# 1_AT32_FOC_CORE_schdoc.net
KiCad netlist of a schematic drawn in Altium Designer
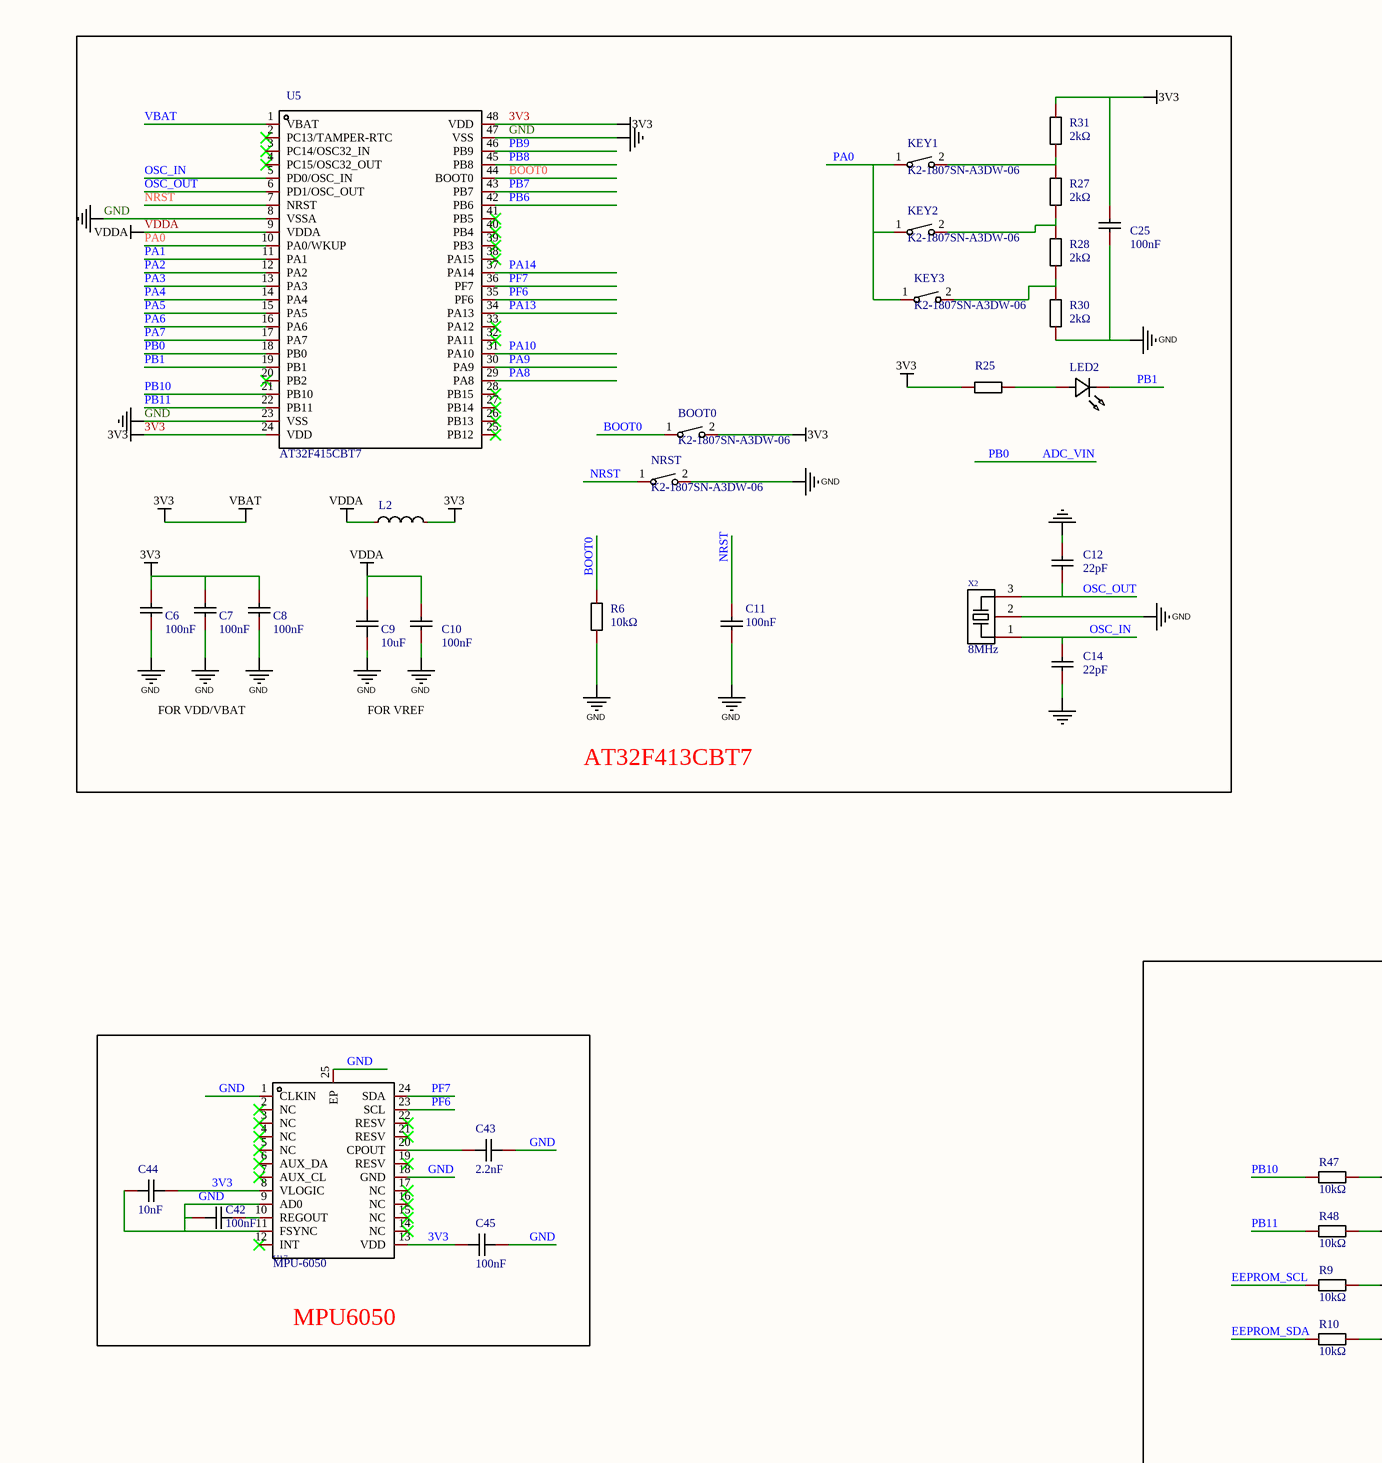
[diagram p0: 1_AT32_FOC_CORE.schdoc.schdoc, top left]
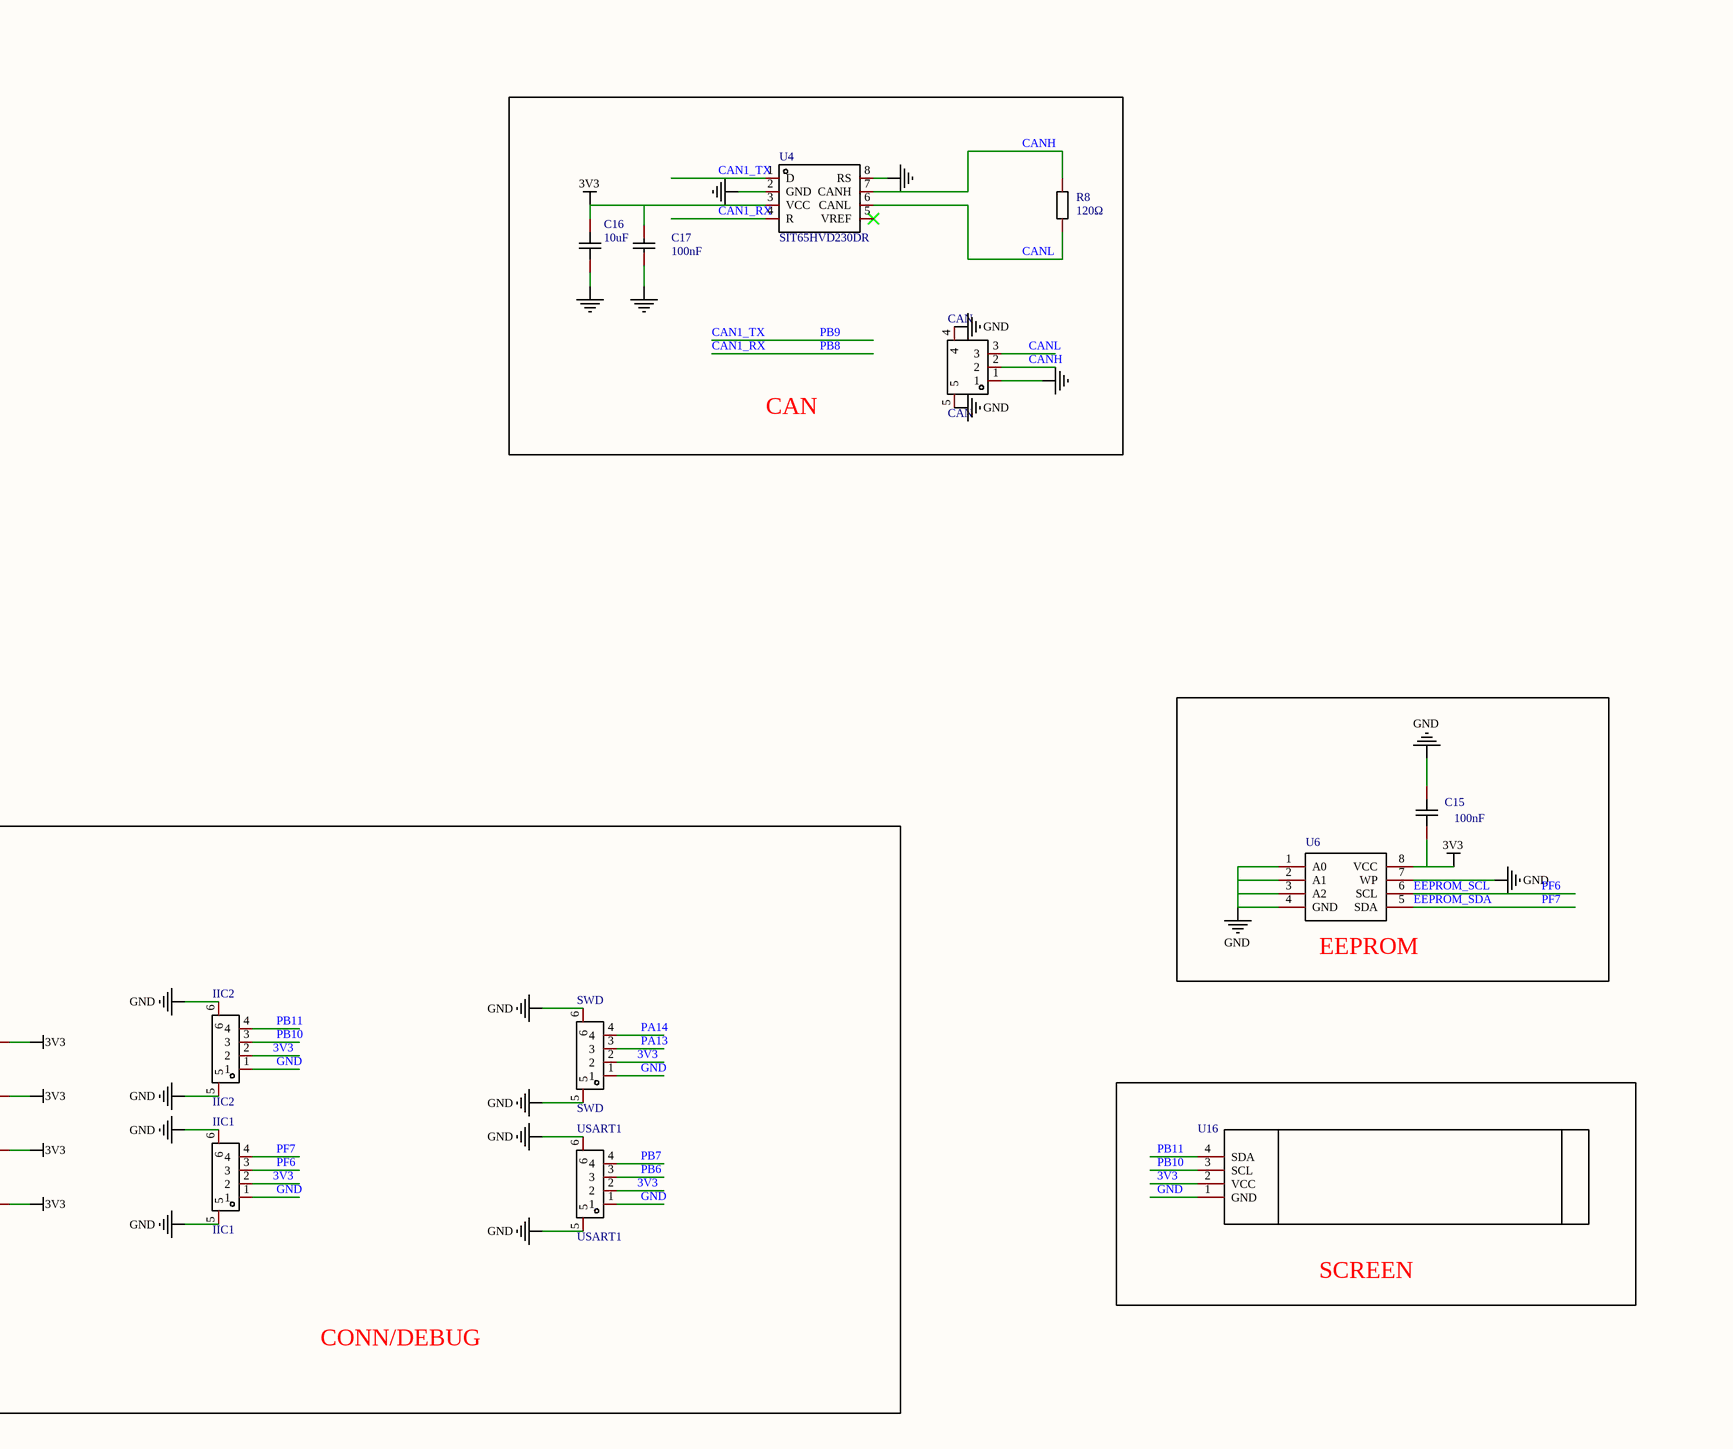
[diagram p1: 1_AT32_FOC_CORE.schdoc.schdoc, top middle]
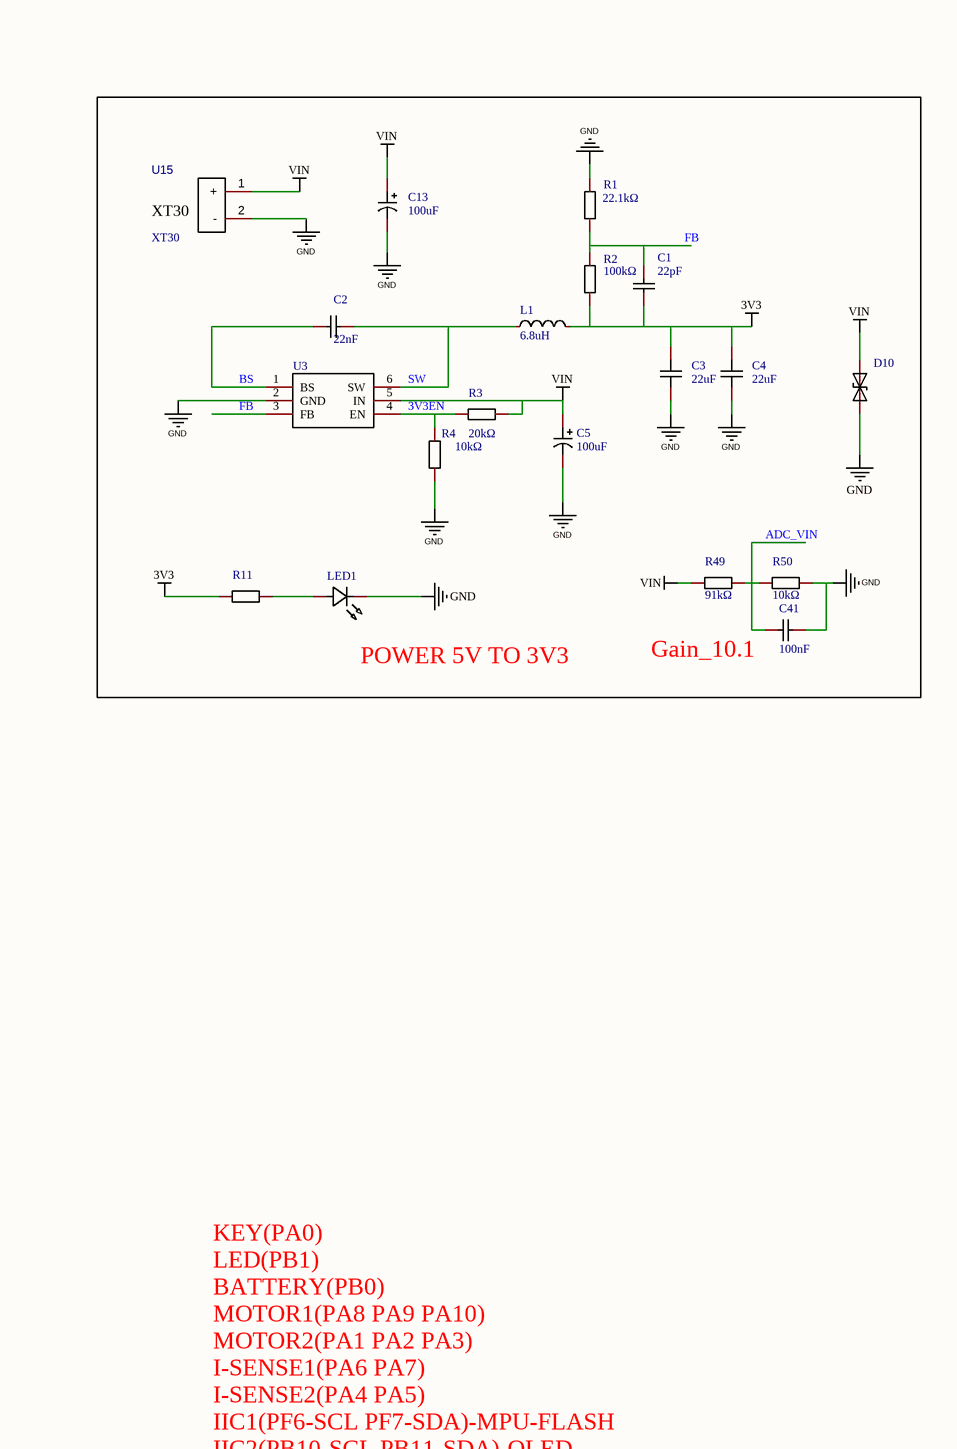
[diagram p2: 1_AT32_FOC_CORE.schdoc.schdoc, top right]
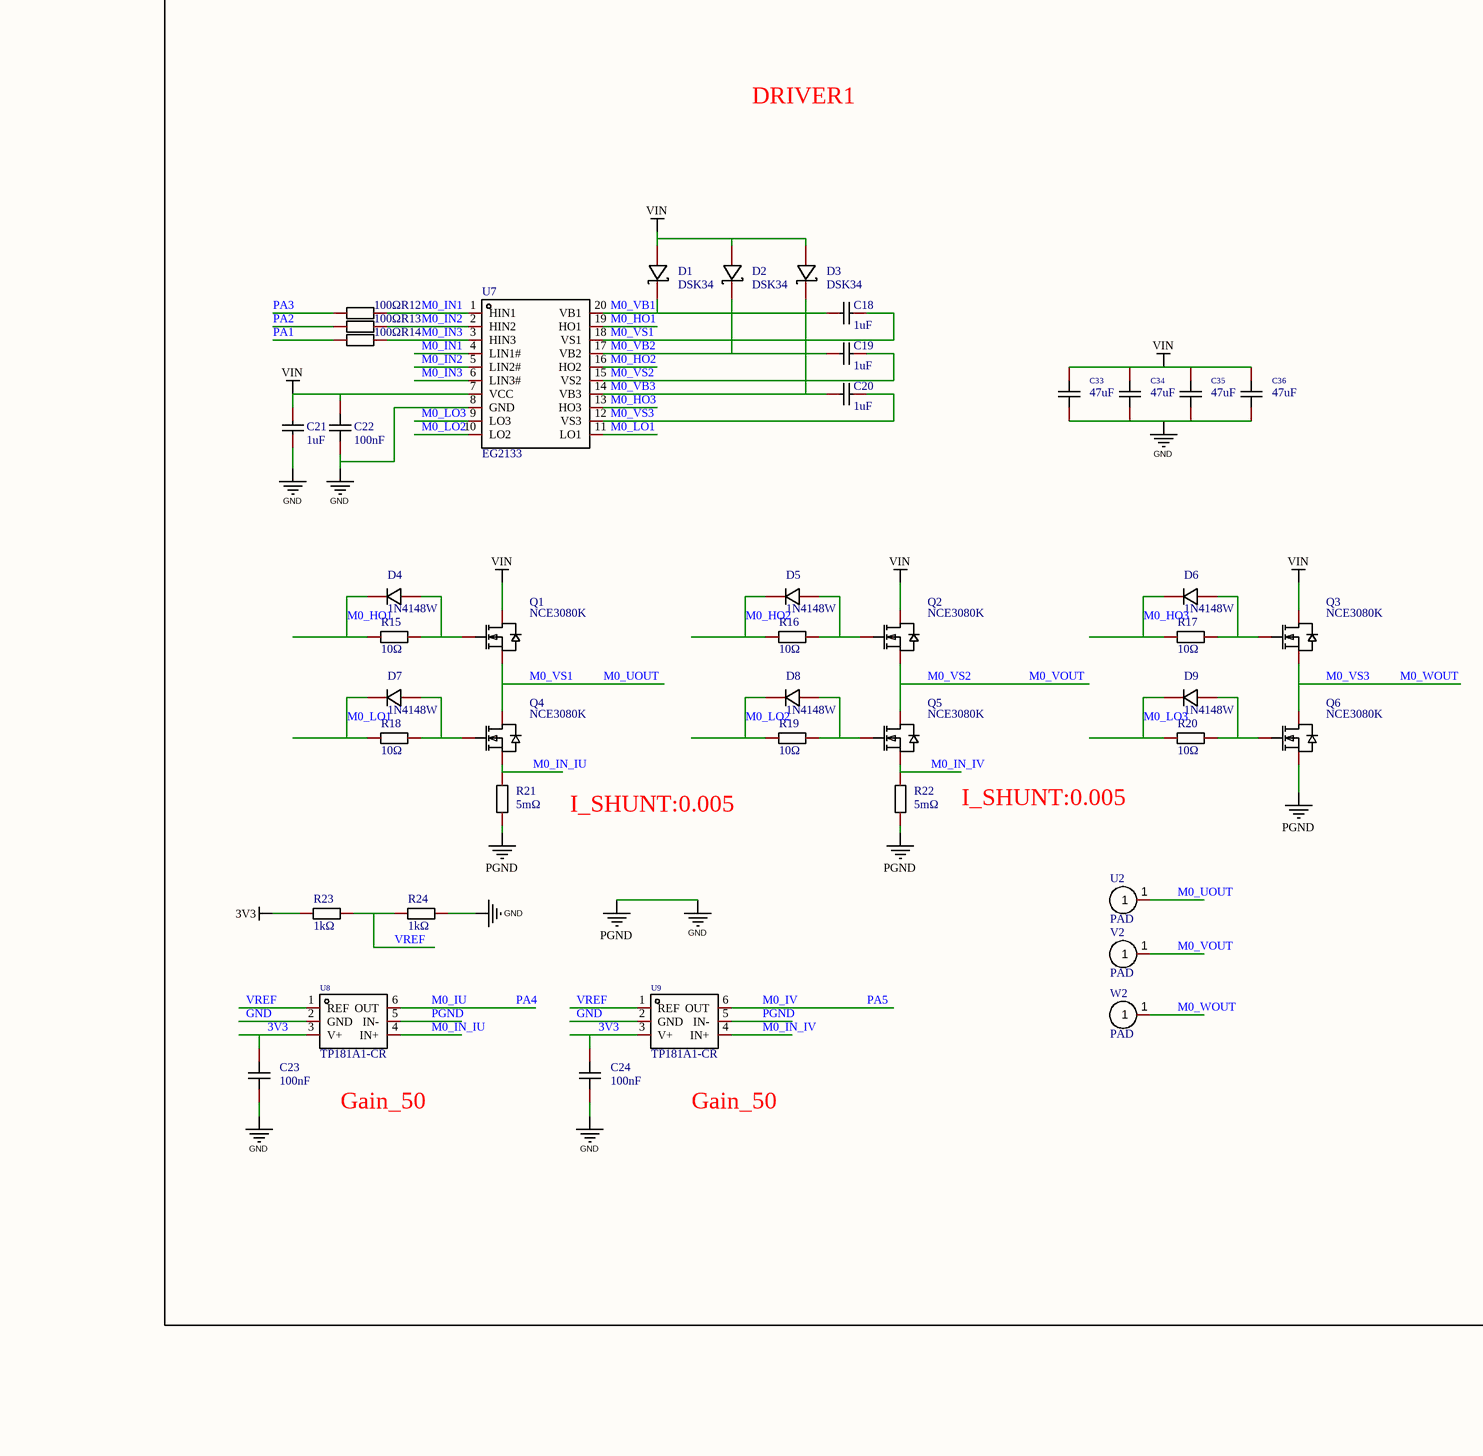
[diagram p3: 1_AT32_FOC_CORE.schdoc.schdoc, bottom left]
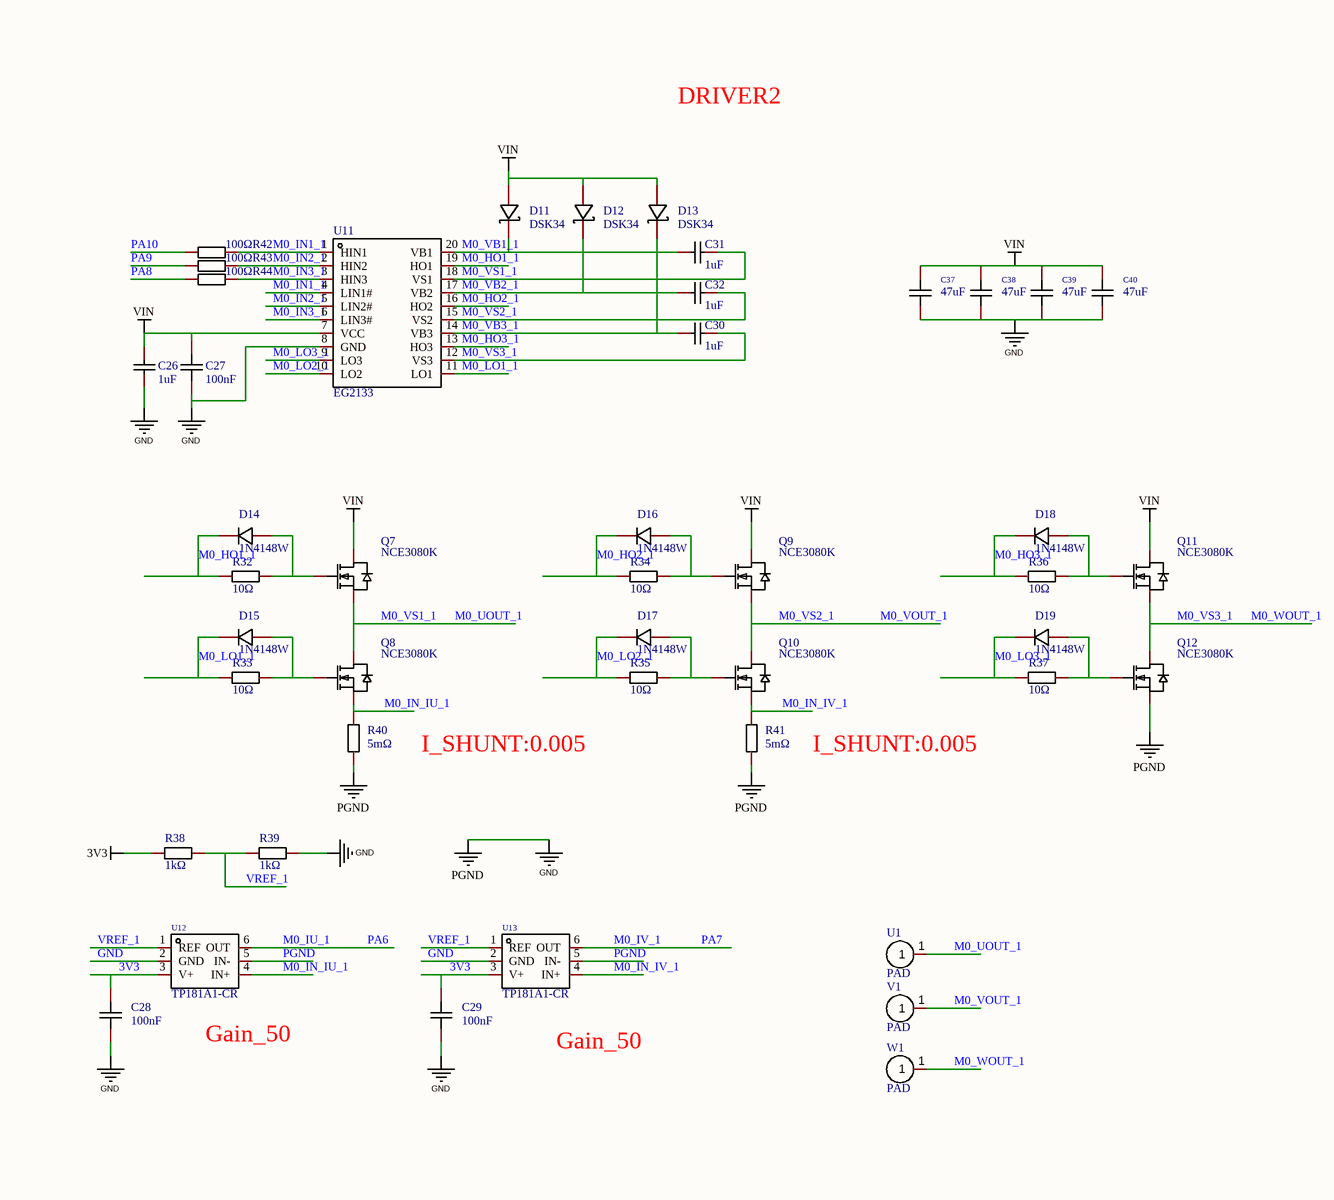
[diagram p4: 1_AT32_FOC_CORE.schdoc.schdoc, bottom middle]

(export (version "E")
  (design (tool "Eeschema 10.0.6"))
  (components
    (comp (ref "BOOT0")
      (value "K2-1807SN-A3DW-06")
      (fields (field (name "NAME") "K2-1807SN-A3DW-06") (field (name "MANUFACTURER") "韩国韩荣"))
      (libsource (lib "altium-import") (part "root_0_K2-1807SN-A3DW-06_"))
    )
    (comp (ref "C1")
      (value "22pF")
      (fields
        (field (name "MANUFACTURER") "SAMSUNG(三星)")
        (field (name "MANUFACTURER PART") "CL10C220JB8NNNC")
        (field (name "TOLERANCE") "±5%")
      )
      (libsource (lib "altium-import") (part "root_1_CL10C220JB8NNNC_"))
    )
    (comp (ref "C2")
      (value "22nF")
      (fields
        (field (name "MANUFACTURER") "SAMSUNG(三星)")
        (field (name "MANUFACTURER PART") "CL10B223KB8NNNC")
        (field (name "TOLERANCE") "±10%")
      )
      (libsource (lib "altium-import") (part "root_0_CL10B223KB8NNNC_"))
    )
    (comp (ref "C3")
      (value "22uF")
      (fields
        (field (name "NAME") "22uF")
        (field (name "MANUFACTURER") "SAMSUNG(三星)")
        (field (name "MANUFACTURER PART") "CL21A226MAQNNNE")
        (field (name "TOLERANCE") "±20%")
      )
      (libsource (lib "altium-import") (part "root_1_CL21A226MAQNNNE_C45783_"))
    )
    (comp (ref "C4")
      (value "22uF")
      (fields
        (field (name "NAME") "22uF")
        (field (name "MANUFACTURER") "SAMSUNG(三星)")
        (field (name "MANUFACTURER PART") "CL21A226MAQNNNE")
        (field (name "TOLERANCE") "±20%")
      )
      (libsource (lib "altium-import") (part "root_1_CL21A226MAQNNNE_C45783_"))
    )
    (comp (ref "C5")
      (value "100uF")
      (fields
        (field (name "NAME") "100uF")
        (field (name "MANUFACTURER") "CapXon(丰宾)")
        (field (name "MANUFACTURER PART") "PM101M025E077PTR")
        (field (name "TOLERANCE") "±20%")
      )
      (libsource (lib "altium-import") (part "root_3_PM101M025E077PTR_"))
    )
    (comp (ref "C6")
      (value "100nF")
      (fields
        (field (name "MANUFACTURER") "FH(风华)")
        (field (name "MANUFACTURER PART") "0603B104K500NT")
        (field (name "TOLERANCE") "±10%")
      )
      (libsource (lib "altium-import") (part "root_1_0603B104K500NT_"))
    )
    (comp (ref "C7")
      (value "100nF")
      (fields
        (field (name "MANUFACTURER") "FH(风华)")
        (field (name "MANUFACTURER PART") "0603B104K500NT")
        (field (name "TOLERANCE") "±10%")
      )
      (libsource (lib "altium-import") (part "root_1_0603B104K500NT_"))
    )
    (comp (ref "C8")
      (value "100nF")
      (fields
        (field (name "MANUFACTURER") "FH(风华)")
        (field (name "MANUFACTURER PART") "0603B104K500NT")
        (field (name "TOLERANCE") "±10%")
      )
      (libsource (lib "altium-import") (part "root_1_0603B104K500NT_"))
    )
    (comp (ref "C9")
      (value "10uF")
      (fields
        (field (name "MANUFACTURER") "SAMSUNG(三星)")
        (field (name "MANUFACTURER PART") "CL10A106KP8NNNC")
        (field (name "TOLERANCE") "±10%")
      )
      (libsource (lib "altium-import") (part "root_1_CL10A106KP8NNNC_"))
    )
    (comp (ref "C10")
      (value "100nF")
      (fields
        (field (name "MANUFACTURER") "FH(风华)")
        (field (name "MANUFACTURER PART") "0603B104K500NT")
        (field (name "TOLERANCE") "±10%")
      )
      (libsource (lib "altium-import") (part "root_1_0603B104K500NT_"))
    )
    (comp (ref "C11")
      (value "100nF")
      (fields
        (field (name "MANUFACTURER") "FH(风华)")
        (field (name "MANUFACTURER PART") "0603B104K500NT")
        (field (name "TOLERANCE") "±10%")
      )
      (libsource (lib "altium-import") (part "root_1_0603B104K500NT_"))
    )
    (comp (ref "C12")
      (value "22pF")
      (fields
        (field (name "MANUFACTURER") "SAMSUNG(三星)")
        (field (name "MANUFACTURER PART") "CL10C220JB8NNNC")
        (field (name "TOLERANCE") "±5%")
      )
      (libsource (lib "altium-import") (part "root_1_CL10C220JB8NNNC_"))
    )
    (comp (ref "C13")
      (value "100uF")
      (fields
        (field (name "NAME") "100uF")
        (field (name "MANUFACTURER") "CapXon(丰宾)")
        (field (name "MANUFACTURER PART") "PM101M025E077PTR")
        (field (name "TOLERANCE") "±20%")
      )
      (libsource (lib "altium-import") (part "root_3_PM101M025E077PTR_"))
    )
    (comp (ref "C14")
      (value "22pF")
      (fields
        (field (name "MANUFACTURER") "SAMSUNG(三星)")
        (field (name "MANUFACTURER PART") "CL10C220JB8NNNC")
        (field (name "TOLERANCE") "±5%")
      )
      (libsource (lib "altium-import") (part "root_1_CL10C220JB8NNNC_"))
    )
    (comp (ref "C15")
      (value "100nF")
      (description "容值:100nF;精度:±10%;额定电压:50V;材质(温度系数):X7R;")
      (fields
        (field (name "MANUFACTURER") "YAGEO(国巨)")
        (field (name "MANUFACTURER PART") "CC0603KRX7R9BB104")
      )
      (libsource (lib "altium-import") (part "root_1_CC0603KRX7R9BB104_"))
    )
    (comp (ref "C16")
      (value "10uF")
      (fields
        (field (name "MANUFACTURER") "SAMSUNG(三星)")
        (field (name "MANUFACTURER PART") "CL10A106KP8NNNC")
        (field (name "TOLERANCE") "±10%")
      )
      (libsource (lib "altium-import") (part "root_1_CL10A106KP8NNNC_"))
    )
    (comp (ref "C17")
      (value "100nF")
      (fields
        (field (name "MANUFACTURER") "FH(风华)")
        (field (name "MANUFACTURER PART") "0603B104K500NT")
        (field (name "TOLERANCE") "±10%")
      )
      (libsource (lib "altium-import") (part "root_1_0603B104K500NT_"))
    )
    (comp (ref "C18")
      (value "1uF")
      (fields
        (field (name "NAME") "1uF")
        (field (name "MANUFACTURER") "SAMSUNG(三星)")
        (field (name "MANUFACTURER PART") "CL10A105KB8NNNC")
        (field (name "TOLERANCE") "±10%")
      )
      (libsource (lib "altium-import") (part "root_2_CL10A105KB8NNNC_"))
    )
    (comp (ref "C19")
      (value "1uF")
      (fields
        (field (name "NAME") "1uF")
        (field (name "MANUFACTURER") "SAMSUNG(三星)")
        (field (name "MANUFACTURER PART") "CL10A105KB8NNNC")
        (field (name "TOLERANCE") "±10%")
      )
      (libsource (lib "altium-import") (part "root_2_CL10A105KB8NNNC_"))
    )
    (comp (ref "C20")
      (value "1uF")
      (fields
        (field (name "NAME") "1uF")
        (field (name "MANUFACTURER") "SAMSUNG(三星)")
        (field (name "MANUFACTURER PART") "CL10A105KB8NNNC")
        (field (name "TOLERANCE") "±10%")
      )
      (libsource (lib "altium-import") (part "root_2_CL10A105KB8NNNC_"))
    )
    (comp (ref "C21")
      (value "1uF")
      (fields
        (field (name "NAME") "1uF")
        (field (name "MANUFACTURER") "SAMSUNG(三星)")
        (field (name "MANUFACTURER PART") "CL10A105KB8NNNC")
        (field (name "TOLERANCE") "±10%")
      )
      (libsource (lib "altium-import") (part "root_1_CL10A105KB8NNNC_"))
    )
    (comp (ref "C22")
      (value "100nF")
      (fields
        (field (name "NAME") "100nF")
        (field (name "MANUFACTURER") "YAGEO(国巨)")
        (field (name "MANUFACTURER PART") "CC0603KRX7R9BB104")
        (field (name "TOLERANCE") "±10%")
      )
      (libsource (lib "altium-import") (part "root_1_CC0603KRX7R9BB104_"))
    )
    (comp (ref "C23")
      (value "100nF")
      (fields
        (field (name "NAME") "100nF")
        (field (name "MANUFACTURER") "YAGEO(国巨)")
        (field (name "MANUFACTURER PART") "CC0603KRX7R9BB104")
        (field (name "TOLERANCE") "±10%")
      )
      (libsource (lib "altium-import") (part "root_3_CC0603KRX7R9BB104_"))
    )
    (comp (ref "C24")
      (value "100nF")
      (fields
        (field (name "NAME") "100nF")
        (field (name "MANUFACTURER") "YAGEO(国巨)")
        (field (name "MANUFACTURER PART") "CC0603KRX7R9BB104")
        (field (name "TOLERANCE") "±10%")
      )
      (libsource (lib "altium-import") (part "root_3_CC0603KRX7R9BB104_"))
    )
    (comp (ref "C25")
      (value "100nF")
      (fields
        (field (name "MANUFACTURER") "FH(风华)")
        (field (name "MANUFACTURER PART") "0603B104K500NT")
        (field (name "TOLERANCE") "±10%")
      )
      (libsource (lib "altium-import") (part "root_1_0603B104K500NT_"))
    )
    (comp (ref "C26")
      (value "1uF")
      (fields
        (field (name "NAME") "1uF")
        (field (name "MANUFACTURER") "SAMSUNG(三星)")
        (field (name "MANUFACTURER PART") "CL10A105KB8NNNC")
        (field (name "TOLERANCE") "±10%")
      )
      (libsource (lib "altium-import") (part "root_1_CL10A105KB8NNNC_"))
    )
    (comp (ref "C27")
      (value "100nF")
      (fields
        (field (name "NAME") "100nF")
        (field (name "MANUFACTURER") "YAGEO(国巨)")
        (field (name "MANUFACTURER PART") "CC0603KRX7R9BB104")
        (field (name "TOLERANCE") "±10%")
      )
      (libsource (lib "altium-import") (part "root_1_CC0603KRX7R9BB104_"))
    )
    (comp (ref "C28")
      (value "100nF")
      (fields
        (field (name "NAME") "100nF")
        (field (name "MANUFACTURER") "YAGEO(国巨)")
        (field (name "MANUFACTURER PART") "CC0603KRX7R9BB104")
        (field (name "TOLERANCE") "±10%")
      )
      (libsource (lib "altium-import") (part "root_3_CC0603KRX7R9BB104_"))
    )
    (comp (ref "C29")
      (value "100nF")
      (fields
        (field (name "NAME") "100nF")
        (field (name "MANUFACTURER") "YAGEO(国巨)")
        (field (name "MANUFACTURER PART") "CC0603KRX7R9BB104")
        (field (name "TOLERANCE") "±10%")
      )
      (libsource (lib "altium-import") (part "root_3_CC0603KRX7R9BB104_"))
    )
    (comp (ref "C30")
      (value "1uF")
      (fields
        (field (name "NAME") "1uF")
        (field (name "MANUFACTURER") "SAMSUNG(三星)")
        (field (name "MANUFACTURER PART") "CL10A105KB8NNNC")
        (field (name "TOLERANCE") "±10%")
      )
      (libsource (lib "altium-import") (part "root_2_CL10A105KB8NNNC_"))
    )
    (comp (ref "C31")
      (value "1uF")
      (fields
        (field (name "NAME") "1uF")
        (field (name "MANUFACTURER") "SAMSUNG(三星)")
        (field (name "MANUFACTURER PART") "CL10A105KB8NNNC")
        (field (name "TOLERANCE") "±10%")
      )
      (libsource (lib "altium-import") (part "root_2_CL10A105KB8NNNC_"))
    )
    (comp (ref "C32")
      (value "1uF")
      (fields
        (field (name "NAME") "1uF")
        (field (name "MANUFACTURER") "SAMSUNG(三星)")
        (field (name "MANUFACTURER PART") "CL10A105KB8NNNC")
        (field (name "TOLERANCE") "±10%")
      )
      (libsource (lib "altium-import") (part "root_2_CL10A105KB8NNNC_"))
    )
    (comp (ref "C33")
      (value "47uF")
      (fields
        (field (name "NAME") "47uF")
        (field (name "MANUFACTURER") "muRata(村田)")
        (field (name "MANUFACTURER PART") "GRM31CR61E476ME44L")
        (field (name "TOLERANCE") "±20%")
      )
      (libsource (lib "altium-import") (part "root_3_GRM31CR61E476ME44L_"))
    )
    (comp (ref "C34")
      (value "47uF")
      (fields
        (field (name "NAME") "47uF")
        (field (name "MANUFACTURER") "muRata(村田)")
        (field (name "MANUFACTURER PART") "GRM31CR61E476ME44L")
        (field (name "TOLERANCE") "±20%")
      )
      (libsource (lib "altium-import") (part "root_3_GRM31CR61E476ME44L_"))
    )
    (comp (ref "C35")
      (value "47uF")
      (fields
        (field (name "NAME") "47uF")
        (field (name "MANUFACTURER") "muRata(村田)")
        (field (name "MANUFACTURER PART") "GRM31CR61E476ME44L")
        (field (name "TOLERANCE") "±20%")
      )
      (libsource (lib "altium-import") (part "root_3_GRM31CR61E476ME44L_"))
    )
    (comp (ref "C36")
      (value "47uF")
      (fields
        (field (name "NAME") "47uF")
        (field (name "MANUFACTURER") "muRata(村田)")
        (field (name "MANUFACTURER PART") "GRM31CR61E476ME44L")
        (field (name "TOLERANCE") "±20%")
      )
      (libsource (lib "altium-import") (part "root_3_GRM31CR61E476ME44L_"))
    )
    (comp (ref "C37")
      (value "47uF")
      (fields
        (field (name "NAME") "47uF")
        (field (name "MANUFACTURER") "muRata(村田)")
        (field (name "MANUFACTURER PART") "GRM31CR61E476ME44L")
        (field (name "TOLERANCE") "±20%")
      )
      (libsource (lib "altium-import") (part "root_3_GRM31CR61E476ME44L_"))
    )
    (comp (ref "C38")
      (value "47uF")
      (fields
        (field (name "NAME") "47uF")
        (field (name "MANUFACTURER") "muRata(村田)")
        (field (name "MANUFACTURER PART") "GRM31CR61E476ME44L")
        (field (name "TOLERANCE") "±20%")
      )
      (libsource (lib "altium-import") (part "root_3_GRM31CR61E476ME44L_"))
    )
    (comp (ref "C39")
      (value "47uF")
      (fields
        (field (name "NAME") "47uF")
        (field (name "MANUFACTURER") "muRata(村田)")
        (field (name "MANUFACTURER PART") "GRM31CR61E476ME44L")
        (field (name "TOLERANCE") "±20%")
      )
      (libsource (lib "altium-import") (part "root_3_GRM31CR61E476ME44L_"))
    )
    (comp (ref "C40")
      (value "47uF")
      (fields
        (field (name "NAME") "47uF")
        (field (name "MANUFACTURER") "muRata(村田)")
        (field (name "MANUFACTURER PART") "GRM31CR61E476ME44L")
        (field (name "TOLERANCE") "±20%")
      )
      (libsource (lib "altium-import") (part "root_3_GRM31CR61E476ME44L_"))
    )
    (comp (ref "C41")
      (value "100nF")
      (fields
        (field (name "MANUFACTURER") "FH(风华)")
        (field (name "MANUFACTURER PART") "0603B104K500NT")
        (field (name "TOLERANCE") "±10%")
      )
      (libsource (lib "altium-import") (part "root_2_0603B104K500NT_"))
    )
    (comp (ref "C42")
      (value "100nF")
      (description "容值:100nF;精度:±10%;额定电压:50V;材质(温度系数):X7R;")
      (fields
        (field (name "MANUFACTURER") "YAGEO(国巨)")
        (field (name "MANUFACTURER PART") "CC0603KRX7R9BB104")
      )
      (libsource (lib "altium-import") (part "root_2_CC0603KRX7R9BB104_"))
    )
    (comp (ref "C43")
      (value "2.2nF")
      (description "容值:100nF;精度:±10%;额定电压:50V;材质(温度系数):X7R;")
      (fields
        (field (name "MANUFACTURER") "YAGEO(国巨)")
        (field (name "MANUFACTURER PART") "CC0603KRX7R9BB104")
      )
      (libsource (lib "altium-import") (part "root_2_CC0603KRX7R9BB104_"))
    )
    (comp (ref "C44")
      (value "10nF")
      (description "容值:100nF;精度:±10%;额定电压:50V;材质(温度系数):X7R;")
      (fields
        (field (name "MANUFACTURER") "YAGEO(国巨)")
        (field (name "MANUFACTURER PART") "CC0603KRX7R9BB104")
      )
      (libsource (lib "altium-import") (part "root_2_CC0603KRX7R9BB104_"))
    )
    (comp (ref "C45")
      (value "100nF")
      (description "容值:100nF;精度:±10%;额定电压:50V;材质(温度系数):X7R;")
      (fields
        (field (name "MANUFACTURER") "YAGEO(国巨)")
        (field (name "MANUFACTURER PART") "CC0603KRX7R9BB104")
      )
      (libsource (lib "altium-import") (part "root_2_CC0603KRX7R9BB104_"))
    )
    (comp (ref "CAN")
      (value "CAN")
      (description "参考系列:SH;间距:1mm;插针结构:1x3P;排数:1;每排PIN数:3;行距:-;公母:公型插针;安装方式:卧贴;额定电流:500mA;工作温度范围:-25℃~+85℃;")
      (fields (field (name "NAME") "CAN") (field (name "MANUFACTURER") "JS(钜硕电子)"))
      (libsource (lib "altium-import") (part "root_2_AFC10-S03QCA-00_"))
    )
    (comp (ref "D1")
      (value "DSK34")
      (description "直流反向耐压(Vr):40V;平均整流电流(Io):3A;正向压降(Vf):550mV@3A;")
      (fields (field (name "NAME") "DSK34") (field (name "MANUFACTURER") "MDD"))
      (libsource (lib "altium-import") (part "root_1_DSK34_C41029_"))
    )
    (comp (ref "D2")
      (value "DSK34")
      (description "直流反向耐压(Vr):40V;平均整流电流(Io):3A;正向压降(Vf):550mV@3A;")
      (fields (field (name "NAME") "DSK34") (field (name "MANUFACTURER") "MDD"))
      (libsource (lib "altium-import") (part "root_1_DSK34_C41029_"))
    )
    (comp (ref "D3")
      (value "DSK34")
      (description "直流反向耐压(Vr):40V;平均整流电流(Io):3A;正向压降(Vf):550mV@3A;")
      (fields (field (name "NAME") "DSK34") (field (name "MANUFACTURER") "MDD"))
      (libsource (lib "altium-import") (part "root_1_DSK34_C41029_"))
    )
    (comp (ref "D4")
      (value "1N4148W")
      (description "二极管配置:独立式;功率:400mW;直流反向耐压(Vr):75V;平均整流电流(Io):150mA;正向压降(Vf):1V@50mA;反向恢复时间(trr):4ns;")
      (fields (field (name "NAME") "1N4148W") (field (name "MANUFACTURER") "ST(先科)"))
      (libsource (lib "altium-import") (part "root_0_1N4148W_C81598_"))
    )
    (comp (ref "D5")
      (value "1N4148W")
      (description "二极管配置:独立式;功率:400mW;直流反向耐压(Vr):75V;平均整流电流(Io):150mA;正向压降(Vf):1V@50mA;反向恢复时间(trr):4ns;")
      (fields (field (name "NAME") "1N4148W") (field (name "MANUFACTURER") "ST(先科)"))
      (libsource (lib "altium-import") (part "root_0_1N4148W_C81598_"))
    )
    (comp (ref "D6")
      (value "1N4148W")
      (description "二极管配置:独立式;功率:400mW;直流反向耐压(Vr):75V;平均整流电流(Io):150mA;正向压降(Vf):1V@50mA;反向恢复时间(trr):4ns;")
      (fields (field (name "NAME") "1N4148W") (field (name "MANUFACTURER") "ST(先科)"))
      (libsource (lib "altium-import") (part "root_0_1N4148W_C81598_"))
    )
    (comp (ref "D7")
      (value "1N4148W")
      (description "二极管配置:独立式;功率:400mW;直流反向耐压(Vr):75V;平均整流电流(Io):150mA;正向压降(Vf):1V@50mA;反向恢复时间(trr):4ns;")
      (fields (field (name "NAME") "1N4148W") (field (name "MANUFACTURER") "ST(先科)"))
      (libsource (lib "altium-import") (part "root_0_1N4148W_C81598_"))
    )
    (comp (ref "D8")
      (value "1N4148W")
      (description "二极管配置:独立式;功率:400mW;直流反向耐压(Vr):75V;平均整流电流(Io):150mA;正向压降(Vf):1V@50mA;反向恢复时间(trr):4ns;")
      (fields (field (name "NAME") "1N4148W") (field (name "MANUFACTURER") "ST(先科)"))
      (libsource (lib "altium-import") (part "root_0_1N4148W_C81598_"))
    )
    (comp (ref "D9")
      (value "1N4148W")
      (description "二极管配置:独立式;功率:400mW;直流反向耐压(Vr):75V;平均整流电流(Io):150mA;正向压降(Vf):1V@50mA;反向恢复时间(trr):4ns;")
      (fields (field (name "NAME") "1N4148W") (field (name "MANUFACTURER") "ST(先科)"))
      (libsource (lib "altium-import") (part "root_0_1N4148W_C81598_"))
    )
    (comp (ref "D10")
      (value "SMAJ12CA/TR13")
      (fields (field (name "MANUFACTURER") "Brightking(君耀电子)"))
      (libsource (lib "altium-import") (part "root_1_SMAJ12CA/TR13_"))
    )
    (comp (ref "D11")
      (value "DSK34")
      (description "直流反向耐压(Vr):40V;平均整流电流(Io):3A;正向压降(Vf):550mV@3A;")
      (fields (field (name "NAME") "DSK34") (field (name "MANUFACTURER") "MDD"))
      (libsource (lib "altium-import") (part "root_1_DSK34_C41029_"))
    )
    (comp (ref "D12")
      (value "DSK34")
      (description "直流反向耐压(Vr):40V;平均整流电流(Io):3A;正向压降(Vf):550mV@3A;")
      (fields (field (name "NAME") "DSK34") (field (name "MANUFACTURER") "MDD"))
      (libsource (lib "altium-import") (part "root_1_DSK34_C41029_"))
    )
    (comp (ref "D13")
      (value "DSK34")
      (description "直流反向耐压(Vr):40V;平均整流电流(Io):3A;正向压降(Vf):550mV@3A;")
      (fields (field (name "NAME") "DSK34") (field (name "MANUFACTURER") "MDD"))
      (libsource (lib "altium-import") (part "root_1_DSK34_C41029_"))
    )
    (comp (ref "D14")
      (value "1N4148W")
      (description "二极管配置:独立式;功率:400mW;直流反向耐压(Vr):75V;平均整流电流(Io):150mA;正向压降(Vf):1V@50mA;反向恢复时间(trr):4ns;")
      (fields (field (name "NAME") "1N4148W") (field (name "MANUFACTURER") "ST(先科)"))
      (libsource (lib "altium-import") (part "root_0_1N4148W_C81598_"))
    )
    (comp (ref "D15")
      (value "1N4148W")
      (description "二极管配置:独立式;功率:400mW;直流反向耐压(Vr):75V;平均整流电流(Io):150mA;正向压降(Vf):1V@50mA;反向恢复时间(trr):4ns;")
      (fields (field (name "NAME") "1N4148W") (field (name "MANUFACTURER") "ST(先科)"))
      (libsource (lib "altium-import") (part "root_0_1N4148W_C81598_"))
    )
    (comp (ref "D16")
      (value "1N4148W")
      (description "二极管配置:独立式;功率:400mW;直流反向耐压(Vr):75V;平均整流电流(Io):150mA;正向压降(Vf):1V@50mA;反向恢复时间(trr):4ns;")
      (fields (field (name "NAME") "1N4148W") (field (name "MANUFACTURER") "ST(先科)"))
      (libsource (lib "altium-import") (part "root_0_1N4148W_C81598_"))
    )
    (comp (ref "D17")
      (value "1N4148W")
      (description "二极管配置:独立式;功率:400mW;直流反向耐压(Vr):75V;平均整流电流(Io):150mA;正向压降(Vf):1V@50mA;反向恢复时间(trr):4ns;")
      (fields (field (name "NAME") "1N4148W") (field (name "MANUFACTURER") "ST(先科)"))
      (libsource (lib "altium-import") (part "root_0_1N4148W_C81598_"))
    )
    (comp (ref "D18")
      (value "1N4148W")
      (description "二极管配置:独立式;功率:400mW;直流反向耐压(Vr):75V;平均整流电流(Io):150mA;正向压降(Vf):1V@50mA;反向恢复时间(trr):4ns;")
      (fields (field (name "NAME") "1N4148W") (field (name "MANUFACTURER") "ST(先科)"))
      (libsource (lib "altium-import") (part "root_0_1N4148W_C81598_"))
    )
    (comp (ref "D19")
      (value "1N4148W")
      (description "二极管配置:独立式;功率:400mW;直流反向耐压(Vr):75V;平均整流电流(Io):150mA;正向压降(Vf):1V@50mA;反向恢复时间(trr):4ns;")
      (fields (field (name "NAME") "1N4148W") (field (name "MANUFACTURER") "ST(先科)"))
      (libsource (lib "altium-import") (part "root_0_1N4148W_C81598_"))
    )
    (comp (ref "IIC1")
      (value "IIC1")
      (description "插针结构:1x4P;间距:1mm;公母:公;安装方式:卧贴;行距:-;排数:1;每排PIN数:4;参考系列:SH;额定电流:500mA;工作温度范围:-25℃~+85℃;")
      (fields (field (name "NAME") "IIC1") (field (name "MANUFACTURER") "JS(钜硕电子)"))
      (libsource (lib "altium-import") (part "root_2_AFC10-S04QCA-00_"))
    )
    (comp (ref "IIC2")
      (value "IIC2")
      (description "插针结构:1x4P;间距:1mm;公母:公;安装方式:卧贴;行距:-;排数:1;每排PIN数:4;参考系列:SH;额定电流:500mA;工作温度范围:-25℃~+85℃;")
      (fields (field (name "NAME") "IIC2") (field (name "MANUFACTURER") "JS(钜硕电子)"))
      (libsource (lib "altium-import") (part "root_2_AFC10-S04QCA-00_"))
    )
    (comp (ref "KEY1")
      (value "K2-1807SN-A3DW-06")
      (fields (field (name "NAME") "K2-1807SN-A3DW-06") (field (name "MANUFACTURER") "韩国韩荣"))
      (libsource (lib "altium-import") (part "root_0_K2-1807SN-A3DW-06_"))
    )
    (comp (ref "KEY2")
      (value "K2-1807SN-A3DW-06")
      (fields (field (name "NAME") "K2-1807SN-A3DW-06") (field (name "MANUFACTURER") "韩国韩荣"))
      (libsource (lib "altium-import") (part "root_0_K2-1807SN-A3DW-06_"))
    )
    (comp (ref "KEY3")
      (value "K2-1807SN-A3DW-06")
      (fields (field (name "NAME") "K2-1807SN-A3DW-06") (field (name "MANUFACTURER") "韩国韩荣"))
      (libsource (lib "altium-import") (part "root_0_K2-1807SN-A3DW-06_"))
    )
    (comp (ref "L1")
      (value "6.8uH")
      (fields (field (name "Comment") "0630 6.8uH"))
      (libsource (lib "altium-import") (part "root_0_0630 6.8uH_"))
    )
    (comp (ref "L2")
      (value "CMH160808B3R3MT")
      (description "电感值:3.3uH;精度:±20%;额定电流:-;直流电阻(DCR):-;")
      (fields (field (name "MANUFACTURER") "FH(风华)") (field (name "TOLERANCE") "±20%"))
      (libsource (lib "altium-import") (part "root_0_CMH160808B3R3MT_"))
    )
    (comp (ref "LED1")
      (value "XL-1608UBC-04")
      (fields (field (name "MANUFACTURER") "XINGLIGHT(成兴光)"))
      (libsource (lib "altium-import") (part "root_2_XL-1608UBC-04_"))
    )
    (comp (ref "LED2")
      (value "XL-1608UBC-04")
      (fields (field (name "MANUFACTURER") "XINGLIGHT(成兴光)"))
      (libsource (lib "altium-import") (part "root_2_XL-1608UBC-04_"))
    )
    (comp (ref "NRST")
      (value "K2-1807SN-A3DW-06")
      (fields (field (name "NAME") "K2-1807SN-A3DW-06") (field (name "MANUFACTURER") "韩国韩荣"))
      (libsource (lib "altium-import") (part "root_0_K2-1807SN-A3DW-06_"))
    )
    (comp (ref "Q1")
      (value "NCE3080K")
      (fields (field (name "NAME") "NCE3080K") (field (name "MANUFACTURER") "NCE(无锡新洁能)"))
      (libsource (lib "altium-import") (part "root_0_NCE3080K_"))
    )
    (comp (ref "Q2")
      (value "NCE3080K")
      (fields (field (name "NAME") "NCE3080K") (field (name "MANUFACTURER") "NCE(无锡新洁能)"))
      (libsource (lib "altium-import") (part "root_0_NCE3080K_"))
    )
    (comp (ref "Q3")
      (value "NCE3080K")
      (fields (field (name "NAME") "NCE3080K") (field (name "MANUFACTURER") "NCE(无锡新洁能)"))
      (libsource (lib "altium-import") (part "root_0_NCE3080K_"))
    )
    (comp (ref "Q4")
      (value "NCE3080K")
      (fields (field (name "NAME") "NCE3080K") (field (name "MANUFACTURER") "NCE(无锡新洁能)"))
      (libsource (lib "altium-import") (part "root_0_NCE3080K_"))
    )
    (comp (ref "Q5")
      (value "NCE3080K")
      (fields (field (name "NAME") "NCE3080K") (field (name "MANUFACTURER") "NCE(无锡新洁能)"))
      (libsource (lib "altium-import") (part "root_0_NCE3080K_"))
    )
    (comp (ref "Q6")
      (value "NCE3080K")
      (fields (field (name "NAME") "NCE3080K") (field (name "MANUFACTURER") "NCE(无锡新洁能)"))
      (libsource (lib "altium-import") (part "root_0_NCE3080K_"))
    )
    (comp (ref "Q7")
      (value "NCE3080K")
      (fields (field (name "NAME") "NCE3080K") (field (name "MANUFACTURER") "NCE(无锡新洁能)"))
      (libsource (lib "altium-import") (part "root_0_NCE3080K_"))
    )
    (comp (ref "Q8")
      (value "NCE3080K")
      (fields (field (name "NAME") "NCE3080K") (field (name "MANUFACTURER") "NCE(无锡新洁能)"))
      (libsource (lib "altium-import") (part "root_0_NCE3080K_"))
    )
    (comp (ref "Q9")
      (value "NCE3080K")
      (fields (field (name "NAME") "NCE3080K") (field (name "MANUFACTURER") "NCE(无锡新洁能)"))
      (libsource (lib "altium-import") (part "root_0_NCE3080K_"))
    )
    (comp (ref "Q10")
      (value "NCE3080K")
      (fields (field (name "NAME") "NCE3080K") (field (name "MANUFACTURER") "NCE(无锡新洁能)"))
      (libsource (lib "altium-import") (part "root_0_NCE3080K_"))
    )
    (comp (ref "Q11")
      (value "NCE3080K")
      (fields (field (name "NAME") "NCE3080K") (field (name "MANUFACTURER") "NCE(无锡新洁能)"))
      (libsource (lib "altium-import") (part "root_0_NCE3080K_"))
    )
    (comp (ref "Q12")
      (value "NCE3080K")
      (fields (field (name "NAME") "NCE3080K") (field (name "MANUFACTURER") "NCE(无锡新洁能)"))
      (libsource (lib "altium-import") (part "root_0_NCE3080K_"))
    )
    (comp (ref "R1")
      (value "22.1kΩ")
      (description "电阻类型:厚膜电阻;阻值:22.1kΩ;精度:±1%;功率:100mW;")
      (fields
        (field (name "MANUFACTURER") "UNI-ROYAL(厚声)")
        (field (name "MANUFACTURER PART") "0603WAF2212T5E")
      )
      (libsource (lib "altium-import") (part "root_1_0603WAF2212T5E_"))
    )
    (comp (ref "R2")
      (value "100kΩ")
      (fields
        (field (name "MANUFACTURER") "UNI-ROYAL(厚声)")
        (field (name "MANUFACTURER PART") "0603WAF1003T5E")
        (field (name "TOLERANCE") "±1%")
      )
      (libsource (lib "altium-import") (part "root_1_0603WAF1003T5E_"))
    )
    (comp (ref "R3")
      (value "20kΩ")
      (fields
        (field (name "MANUFACTURER") "UNI-ROYAL(厚声)")
        (field (name "MANUFACTURER PART") "0603WAF2002T5E")
        (field (name "TOLERANCE") "±1%")
      )
      (libsource (lib "altium-import") (part "root_0_0603WAF2002T5E_"))
    )
    (comp (ref "R4")
      (value "10kΩ")
      (description "电阻类型:厚膜电阻;阻值:10kΩ;精度:±1%;功率:100mW;温度系数:±100ppm/℃;最大工作电压:75V;工作温度范围:-55℃~+155℃;")
      (fields
        (field (name "MANUFACTURER") "UNI-ROYAL(厚声)")
        (field (name "MANUFACTURER PART") "0603WAF1002T5E")
      )
      (libsource (lib "altium-import") (part "root_1_0603WAF1002T5E_"))
    )
    (comp (ref "R6")
      (value "10kΩ")
      (fields
        (field (name "MANUFACTURER") "UNI-ROYAL(厚声)")
        (field (name "MANUFACTURER PART") "0603WAF1002T5E")
        (field (name "TOLERANCE") "±1%")
      )
      (libsource (lib "altium-import") (part "root_1_0603WAF1002T5E_"))
    )
    (comp (ref "R8")
      (value "120Ω")
      (fields
        (field (name "MANUFACTURER") "UNI-ROYAL(厚声)")
        (field (name "MANUFACTURER PART") "0603WAF1200T5E")
        (field (name "TOLERANCE") "±1%")
      )
      (libsource (lib "altium-import") (part "root_3_0603WAF1200T5E_"))
    )
    (comp (ref "R9")
      (value "10kΩ")
      (fields
        (field (name "NAME") "10kΩ")
        (field (name "MANUFACTURER") "UNI-ROYAL(厚声)")
        (field (name "MANUFACTURER PART") "0603WAF1002T5E")
        (field (name "TOLERANCE") "±1%")
      )
      (libsource (lib "altium-import") (part "root_0_0603WAF1002T5E_"))
    )
    (comp (ref "R10")
      (value "10kΩ")
      (fields
        (field (name "NAME") "10kΩ")
        (field (name "MANUFACTURER") "UNI-ROYAL(厚声)")
        (field (name "MANUFACTURER PART") "0603WAF1002T5E")
        (field (name "TOLERANCE") "±1%")
      )
      (libsource (lib "altium-import") (part "root_0_0603WAF1002T5E_"))
    )
    (comp (ref "R11")
      (value "5.1kΩ")
      (description "电阻类型:厚膜电阻;阻值:5.1kΩ;精度:±1%;功率:100mW;温度系数:±100ppm/℃;")
      (fields
        (field (name "MANUFACTURER PART") "0603WAF5101T5E")
        (field (name "MANUFACTURER") "UNI-ROYAL(厚声)")
      )
      (libsource (lib "altium-import") (part "root_0_0603WAF5101T5E_"))
    )
    (comp (ref "R12")
      (value "100Ω")
      (description "电阻类型:厚膜电阻;阻值:100Ω;精度:±1%;功率:100mW;")
      (fields
        (field (name "MANUFACTURER") "UNI-ROYAL(厚声)")
        (field (name "MANUFACTURER PART") "0603WAF1000T5E")
      )
      (libsource (lib "altium-import") (part "root_0_0603WAF1000T5E_"))
    )
    (comp (ref "R13")
      (value "100Ω")
      (description "电阻类型:厚膜电阻;阻值:100Ω;精度:±1%;功率:100mW;")
      (fields
        (field (name "MANUFACTURER") "UNI-ROYAL(厚声)")
        (field (name "MANUFACTURER PART") "0603WAF1000T5E")
      )
      (libsource (lib "altium-import") (part "root_0_0603WAF1000T5E_"))
    )
    (comp (ref "R14")
      (value "100Ω")
      (description "电阻类型:厚膜电阻;阻值:100Ω;精度:±1%;功率:100mW;")
      (fields
        (field (name "MANUFACTURER") "UNI-ROYAL(厚声)")
        (field (name "MANUFACTURER PART") "0603WAF1000T5E")
      )
      (libsource (lib "altium-import") (part "root_0_0603WAF1000T5E_"))
    )
    (comp (ref "R15")
      (value "10Ω")
      (fields
        (field (name "NAME") "10Ω")
        (field (name "MANUFACTURER") "UNI-ROYAL(厚声)")
        (field (name "MANUFACTURER PART") "0805W8F100JT5E")
        (field (name "TOLERANCE") "±1%")
      )
      (libsource (lib "altium-import") (part "root_0_0805W8F100JT5E_"))
    )
    (comp (ref "R16")
      (value "10Ω")
      (fields
        (field (name "NAME") "10Ω")
        (field (name "MANUFACTURER") "UNI-ROYAL(厚声)")
        (field (name "MANUFACTURER PART") "0805W8F100JT5E")
        (field (name "TOLERANCE") "±1%")
      )
      (libsource (lib "altium-import") (part "root_0_0805W8F100JT5E_"))
    )
    (comp (ref "R17")
      (value "10Ω")
      (fields
        (field (name "NAME") "10Ω")
        (field (name "MANUFACTURER") "UNI-ROYAL(厚声)")
        (field (name "MANUFACTURER PART") "0805W8F100JT5E")
        (field (name "TOLERANCE") "±1%")
      )
      (libsource (lib "altium-import") (part "root_0_0805W8F100JT5E_"))
    )
    (comp (ref "R18")
      (value "10Ω")
      (fields
        (field (name "NAME") "10Ω")
        (field (name "MANUFACTURER") "UNI-ROYAL(厚声)")
        (field (name "MANUFACTURER PART") "0805W8F100JT5E")
        (field (name "TOLERANCE") "±1%")
      )
      (libsource (lib "altium-import") (part "root_0_0805W8F100JT5E_"))
    )
    (comp (ref "R19")
      (value "10Ω")
      (fields
        (field (name "NAME") "10Ω")
        (field (name "MANUFACTURER") "UNI-ROYAL(厚声)")
        (field (name "MANUFACTURER PART") "0805W8F100JT5E")
        (field (name "TOLERANCE") "±1%")
      )
      (libsource (lib "altium-import") (part "root_0_0805W8F100JT5E_"))
    )
    (comp (ref "R20")
      (value "10Ω")
      (fields
        (field (name "NAME") "10Ω")
        (field (name "MANUFACTURER") "UNI-ROYAL(厚声)")
        (field (name "MANUFACTURER PART") "0805W8F100JT5E")
        (field (name "TOLERANCE") "±1%")
      )
      (libsource (lib "altium-import") (part "root_0_0805W8F100JT5E_"))
    )
    (comp (ref "R21")
      (value "5mΩ")
      (fields
        (field (name "NAME") "5mΩ")
        (field (name "MANUFACTURER") "大毅科技")
        (field (name "MANUFACTURER PART") "RLP25FEER005")
        (field (name "TOLERANCE") "±1%")
      )
      (libsource (lib "altium-import") (part "root_1_RLP25FEER005_"))
    )
    (comp (ref "R22")
      (value "5mΩ")
      (fields
        (field (name "NAME") "5mΩ")
        (field (name "MANUFACTURER") "大毅科技")
        (field (name "MANUFACTURER PART") "RLP25FEER005")
        (field (name "TOLERANCE") "±1%")
      )
      (libsource (lib "altium-import") (part "root_1_RLP25FEER005_"))
    )
    (comp (ref "R23")
      (value "1kΩ")
      (fields
        (field (name "NAME") "1kΩ")
        (field (name "MANUFACTURER") "UNI-ROYAL(厚声)")
        (field (name "MANUFACTURER PART") "0603WAF1001T5E")
        (field (name "TOLERANCE") "±1%")
      )
      (libsource (lib "altium-import") (part "root_0_0603WAF1001T5E_"))
    )
    (comp (ref "R24")
      (value "1kΩ")
      (fields
        (field (name "NAME") "1kΩ")
        (field (name "MANUFACTURER") "UNI-ROYAL(厚声)")
        (field (name "MANUFACTURER PART") "0603WAF1001T5E")
        (field (name "TOLERANCE") "±1%")
      )
      (libsource (lib "altium-import") (part "root_0_0603WAF1001T5E_"))
    )
    (comp (ref "R25")
      (value "5.1kΩ")
      (description "电阻类型:厚膜电阻;阻值:5.1kΩ;精度:±1%;功率:100mW;温度系数:±100ppm/℃;")
      (fields
        (field (name "MANUFACTURER PART") "0603WAF5101T5E")
        (field (name "MANUFACTURER") "UNI-ROYAL(厚声)")
      )
      (libsource (lib "altium-import") (part "root_0_0603WAF5101T5E_"))
    )
    (comp (ref "R27")
      (value "2kΩ")
      (fields
        (field (name "MANUFACTURER") "UNI-ROYAL(厚声)")
        (field (name "MANUFACTURER PART") "0603WAF1002T5E")
        (field (name "TOLERANCE") "±1%")
      )
      (libsource (lib "altium-import") (part "root_1_0603WAF1002T5E_"))
    )
    (comp (ref "R28")
      (value "2kΩ")
      (fields
        (field (name "MANUFACTURER") "UNI-ROYAL(厚声)")
        (field (name "MANUFACTURER PART") "0603WAF1002T5E")
        (field (name "TOLERANCE") "±1%")
      )
      (libsource (lib "altium-import") (part "root_1_0603WAF1002T5E_"))
    )
    (comp (ref "R30")
      (value "2kΩ")
      (fields
        (field (name "MANUFACTURER") "UNI-ROYAL(厚声)")
        (field (name "MANUFACTURER PART") "0603WAF1002T5E")
        (field (name "TOLERANCE") "±1%")
      )
      (libsource (lib "altium-import") (part "root_1_0603WAF1002T5E_"))
    )
    (comp (ref "R31")
      (value "2kΩ")
      (fields
        (field (name "MANUFACTURER") "UNI-ROYAL(厚声)")
        (field (name "MANUFACTURER PART") "0603WAF1002T5E")
        (field (name "TOLERANCE") "±1%")
      )
      (libsource (lib "altium-import") (part "root_1_0603WAF1002T5E_"))
    )
    (comp (ref "R32")
      (value "10Ω")
      (fields
        (field (name "NAME") "10Ω")
        (field (name "MANUFACTURER") "UNI-ROYAL(厚声)")
        (field (name "MANUFACTURER PART") "0805W8F100JT5E")
        (field (name "TOLERANCE") "±1%")
      )
      (libsource (lib "altium-import") (part "root_0_0805W8F100JT5E_"))
    )
    (comp (ref "R33")
      (value "10Ω")
      (fields
        (field (name "NAME") "10Ω")
        (field (name "MANUFACTURER") "UNI-ROYAL(厚声)")
        (field (name "MANUFACTURER PART") "0805W8F100JT5E")
        (field (name "TOLERANCE") "±1%")
      )
      (libsource (lib "altium-import") (part "root_0_0805W8F100JT5E_"))
    )
    (comp (ref "R34")
      (value "10Ω")
      (fields
        (field (name "NAME") "10Ω")
        (field (name "MANUFACTURER") "UNI-ROYAL(厚声)")
        (field (name "MANUFACTURER PART") "0805W8F100JT5E")
        (field (name "TOLERANCE") "±1%")
      )
      (libsource (lib "altium-import") (part "root_0_0805W8F100JT5E_"))
    )
    (comp (ref "R35")
      (value "10Ω")
      (fields
        (field (name "NAME") "10Ω")
        (field (name "MANUFACTURER") "UNI-ROYAL(厚声)")
        (field (name "MANUFACTURER PART") "0805W8F100JT5E")
        (field (name "TOLERANCE") "±1%")
      )
      (libsource (lib "altium-import") (part "root_0_0805W8F100JT5E_"))
    )
    (comp (ref "R36")
      (value "10Ω")
      (fields
        (field (name "NAME") "10Ω")
        (field (name "MANUFACTURER") "UNI-ROYAL(厚声)")
        (field (name "MANUFACTURER PART") "0805W8F100JT5E")
        (field (name "TOLERANCE") "±1%")
      )
      (libsource (lib "altium-import") (part "root_0_0805W8F100JT5E_"))
    )
    (comp (ref "R37")
      (value "10Ω")
      (fields
        (field (name "NAME") "10Ω")
        (field (name "MANUFACTURER") "UNI-ROYAL(厚声)")
        (field (name "MANUFACTURER PART") "0805W8F100JT5E")
        (field (name "TOLERANCE") "±1%")
      )
      (libsource (lib "altium-import") (part "root_0_0805W8F100JT5E_"))
    )
    (comp (ref "R38")
      (value "1kΩ")
      (fields
        (field (name "NAME") "1kΩ")
        (field (name "MANUFACTURER") "UNI-ROYAL(厚声)")
        (field (name "MANUFACTURER PART") "0603WAF1001T5E")
        (field (name "TOLERANCE") "±1%")
      )
      (libsource (lib "altium-import") (part "root_0_0603WAF1001T5E_"))
    )
    (comp (ref "R39")
      (value "1kΩ")
      (fields
        (field (name "NAME") "1kΩ")
        (field (name "MANUFACTURER") "UNI-ROYAL(厚声)")
        (field (name "MANUFACTURER PART") "0603WAF1001T5E")
        (field (name "TOLERANCE") "±1%")
      )
      (libsource (lib "altium-import") (part "root_0_0603WAF1001T5E_"))
    )
    (comp (ref "R40")
      (value "5mΩ")
      (fields
        (field (name "NAME") "5mΩ")
        (field (name "MANUFACTURER") "大毅科技")
        (field (name "MANUFACTURER PART") "RLP25FEER005")
        (field (name "TOLERANCE") "±1%")
      )
      (libsource (lib "altium-import") (part "root_1_RLP25FEER005_"))
    )
    (comp (ref "R41")
      (value "5mΩ")
      (fields
        (field (name "NAME") "5mΩ")
        (field (name "MANUFACTURER") "大毅科技")
        (field (name "MANUFACTURER PART") "RLP25FEER005")
        (field (name "TOLERANCE") "±1%")
      )
      (libsource (lib "altium-import") (part "root_1_RLP25FEER005_"))
    )
    (comp (ref "R42")
      (value "100Ω")
      (description "电阻类型:厚膜电阻;阻值:100Ω;精度:±1%;功率:100mW;")
      (fields
        (field (name "MANUFACTURER") "UNI-ROYAL(厚声)")
        (field (name "MANUFACTURER PART") "0603WAF1000T5E")
      )
      (libsource (lib "altium-import") (part "root_0_0603WAF1000T5E_"))
    )
    (comp (ref "R43")
      (value "100Ω")
      (description "电阻类型:厚膜电阻;阻值:100Ω;精度:±1%;功率:100mW;")
      (fields
        (field (name "MANUFACTURER") "UNI-ROYAL(厚声)")
        (field (name "MANUFACTURER PART") "0603WAF1000T5E")
      )
      (libsource (lib "altium-import") (part "root_0_0603WAF1000T5E_"))
    )
    (comp (ref "R44")
      (value "100Ω")
      (description "电阻类型:厚膜电阻;阻值:100Ω;精度:±1%;功率:100mW;")
      (fields
        (field (name "MANUFACTURER") "UNI-ROYAL(厚声)")
        (field (name "MANUFACTURER PART") "0603WAF1000T5E")
      )
      (libsource (lib "altium-import") (part "root_0_0603WAF1000T5E_"))
    )
    (comp (ref "R47")
      (value "10kΩ")
      (fields
        (field (name "NAME") "10kΩ")
        (field (name "MANUFACTURER") "UNI-ROYAL(厚声)")
        (field (name "MANUFACTURER PART") "0603WAF1002T5E")
        (field (name "TOLERANCE") "±1%")
      )
      (libsource (lib "altium-import") (part "root_0_0603WAF1002T5E_"))
    )
    (comp (ref "R48")
      (value "10kΩ")
      (fields
        (field (name "NAME") "10kΩ")
        (field (name "MANUFACTURER") "UNI-ROYAL(厚声)")
        (field (name "MANUFACTURER PART") "0603WAF1002T5E")
        (field (name "TOLERANCE") "±1%")
      )
      (libsource (lib "altium-import") (part "root_0_0603WAF1002T5E_"))
    )
    (comp (ref "R49")
      (value "91kΩ")
      (description "电阻类型:厚膜电阻;阻值:5.1kΩ;精度:±1%;功率:100mW;温度系数:±100ppm/℃;")
      (fields
        (field (name "MANUFACTURER PART") "0603WAF5101T5E")
        (field (name "MANUFACTURER") "UNI-ROYAL(厚声)")
      )
      (libsource (lib "altium-import") (part "root_0_0603WAF5101T5E_"))
    )
    (comp (ref "R50")
      (value "10kΩ")
      (description "电阻类型:厚膜电阻;阻值:5.1kΩ;精度:±1%;功率:100mW;温度系数:±100ppm/℃;")
      (fields
        (field (name "MANUFACTURER PART") "0603WAF5101T5E")
        (field (name "MANUFACTURER") "UNI-ROYAL(厚声)")
      )
      (libsource (lib "altium-import") (part "root_0_0603WAF5101T5E_"))
    )
    (comp (ref "SWD")
      (value "SWD")
      (description "插针结构:1x4P;间距:1mm;公母:公;安装方式:卧贴;行距:-;排数:1;每排PIN数:4;参考系列:SH;额定电流:500mA;工作温度范围:-25℃~+85℃;")
      (fields (field (name "NAME") "SWD") (field (name "MANUFACTURER") "JS(钜硕电子)"))
      (libsource (lib "altium-import") (part "root_2_AFC10-S04QCA-00_"))
    )
    (comp (ref "U1")
      (value "PAD")
      (fields (field (name "NAME") "PAD"))
      (libsource (lib "altium-import") (part "root_1_PAD_"))
    )
    (comp (ref "U2")
      (value "PAD")
      (fields (field (name "NAME") "PAD"))
      (libsource (lib "altium-import") (part "root_1_PAD_"))
    )
    (comp (ref "U3")
      (value "MT2492")
      (description "功能类型:降压型;同步整流:-;输出通道数:-;拓扑结构:-;输入电压:-;输出电流(最大值):-;开关频率:-;")
      (fields (field (name "MANUFACTURER") "西安航天民芯"))
      (libsource (lib "altium-import") (part "root_0_MT2492_"))
    )
    (comp (ref "U4")
      (value "SIT65HVD230DR")
      (description "类型:-;")
      (fields (field (name "NAME") "SIT65HVD230DR") (field (name "MANUFACTURER") "SIT(芯力特)"))
      (libsource (lib "altium-import") (part "root_0_SIT65HVD230DR_"))
    )
    (comp (ref "U5")
      (value "AT32F415CBT7")
      (description "CPU内核:ARM Cortex-M4;CPU最大主频:-;程序存储容量:128KB;程序存储器类型:FLASH;RAM总容量:32KB;GPIO端口数量:-;")
      (fields (field (name "MANUFACTURER") "ARTERY(雅特力)") (field (name "MANUFACTURER PART") "AT32F415CBT7"))
      (libsource (lib "altium-import") (part "root_0_AT32F415CBT7_C528427_"))
    )
    (comp (ref "U6")
      (value "AT24C02C-SSHM-T")
      (description "存储器容量:2Kb (256 x 8);存储器接口类型:I2C;工作电压:1.7V ~ 5.5V;")
      (fields (field (name "MANUFACTURER") "MICROCHIP(美国微芯)"))
      (libsource (lib "altium-import") (part "root_0_AT24C02C-SSHM-T_"))
    )
    (comp (ref "U7")
      (value "EG2133")
      (description "EG2133是一款高性价比的三相半桥驱动芯片，配合六颗Nmos可以组成三相直流无刷电机驱动器。")
      (fields (field (name "NAME") "EG2133") (field (name "MANUFACTURER") "EG(屹晶微)"))
      (libsource (lib "altium-import") (part "root_0_EG2133_C190343_"))
    )
    (comp (ref "U8")
      (value "TP181A1-CR")
      (fields (field (name "NAME") "TP181A1-CR") (field (name "MANUFACTURER") "3PEAK"))
      (libsource (lib "altium-import") (part "root_0_TP181A1-CR_"))
    )
    (comp (ref "U9")
      (value "TP181A1-CR")
      (fields (field (name "NAME") "TP181A1-CR") (field (name "MANUFACTURER") "3PEAK"))
      (libsource (lib "altium-import") (part "root_0_TP181A1-CR_"))
    )
    (comp (ref "U11")
      (value "EG2133")
      (description "EG2133是一款高性价比的三相半桥驱动芯片，配合六颗Nmos可以组成三相直流无刷电机驱动器。")
      (fields (field (name "NAME") "EG2133") (field (name "MANUFACTURER") "EG(屹晶微)"))
      (libsource (lib "altium-import") (part "root_0_EG2133_C190343_"))
    )
    (comp (ref "U12")
      (value "TP181A1-CR")
      (fields (field (name "NAME") "TP181A1-CR") (field (name "MANUFACTURER") "3PEAK"))
      (libsource (lib "altium-import") (part "root_0_TP181A1-CR_"))
    )
    (comp (ref "U13")
      (value "TP181A1-CR")
      (fields (field (name "NAME") "TP181A1-CR") (field (name "MANUFACTURER") "3PEAK"))
      (libsource (lib "altium-import") (part "root_0_TP181A1-CR_"))
    )
    (comp (ref "U15")
      (value "XT30")
      (fields (field (name "NAME") "XT30"))
      (libsource (lib "altium-import") (part "root_0_XT30_"))
    )
    (comp (ref "U16")
      (value "0.91OLED-4P-IIC模块")
      (libsource (lib "altium-import") (part "root_0_0.91OLED-4P-IIC模块_"))
    )
    (comp (ref "U17")
      (value "MPU-6050")
      (description "三轴加速度计和三轴陀螺仪，工作电压：2.375V~3.46V")
      (fields (field (name "NAME") "MPU-6050") (field (name "MANUFACTURER") "TDK InvenSense(应美盛)"))
      (libsource (lib "altium-import") (part "root_0_MPU-6050_"))
    )
    (comp (ref "USART1")
      (value "USART1")
      (description "插针结构:1x4P;间距:1mm;公母:公;安装方式:卧贴;行距:-;排数:1;每排PIN数:4;参考系列:SH;额定电流:500mA;工作温度范围:-25℃~+85℃;")
      (fields (field (name "NAME") "USART1") (field (name "MANUFACTURER") "JS(钜硕电子)"))
      (libsource (lib "altium-import") (part "root_2_AFC10-S04QCA-00_"))
    )
    (comp (ref "V1")
      (value "PAD")
      (fields (field (name "NAME") "PAD"))
      (libsource (lib "altium-import") (part "root_1_PAD_"))
    )
    (comp (ref "V2")
      (value "PAD")
      (fields (field (name "NAME") "PAD"))
      (libsource (lib "altium-import") (part "root_1_PAD_"))
    )
    (comp (ref "W1")
      (value "PAD")
      (fields (field (name "NAME") "PAD"))
      (libsource (lib "altium-import") (part "root_1_PAD_"))
    )
    (comp (ref "W2")
      (value "PAD")
      (fields (field (name "NAME") "PAD"))
      (libsource (lib "altium-import") (part "root_1_PAD_"))
    )
    (comp (ref "X2")
      (value "8MHz")
      (description "频率:8MHz;频率容差:±0.5%;内置负载电容:10pF;谐振阻抗:40Ω;")
      (fields
        (field (name "NAME") "8MHz")
        (field (name "MANUFACTURER PART") "CSTCE8M00G52-R0")
        (field (name "MANUFACTURER") "muRata(村田)")
      )
      (libsource (lib "altium-import") (part "root_1_CSTCE8M00G52-R0_"))
    )
  )
  (nets
    (net (code "1") (name "/3V3EN") (class "Default")
      (node (ref "R3") (pin "1") (pinfunction "1_1") (pintype "passive"))
      (node (ref "R4") (pin "2") (pinfunction "2_2") (pintype "passive"))
      (node (ref "U3") (pin "4") (pinfunction "EN_4") (pintype "passive"))
    )
    (net (code "2") (name "/ADC_VIN") (class "Default")
      (node (ref "C41") (pin "2") (pinfunction "2_2") (pintype "passive"))
      (node (ref "R49") (pin "2") (pinfunction "2_2") (pintype "passive"))
      (node (ref "R50") (pin "1") (pinfunction "1_1") (pintype "passive"))
      (node (ref "U5") (pin "18") (pinfunction "PB0_18") (pintype "passive"))
    )
    (net (code "3") (name "/BOOT0") (class "Default")
      (node (ref "BOOT0") (pin "1") (pinfunction "1_1") (pintype "passive"))
      (node (ref "R6") (pin "2") (pinfunction "2_2") (pintype "passive"))
      (node (ref "U5") (pin "44") (pinfunction "BOOT0_44") (pintype "passive"))
    )
    (net (code "4") (name "/BS") (class "Default")
      (node (ref "C2") (pin "1") (pinfunction "1_1") (pintype "passive"))
      (node (ref "U3") (pin "1") (pinfunction "BS_1") (pintype "passive"))
    )
    (net (code "5") (name "/CAN1_RX") (class "Default")
      (node (ref "U4") (pin "4") (pinfunction "R_4") (pintype "passive"))
      (node (ref "U5") (pin "45") (pinfunction "PB8_45") (pintype "passive"))
    )
    (net (code "6") (name "/CAN1_TX") (class "Default")
      (node (ref "U4") (pin "1") (pinfunction "D_1") (pintype "passive"))
      (node (ref "U5") (pin "46") (pinfunction "PB9_46") (pintype "passive"))
    )
    (net (code "7") (name "/CANH") (class "Default")
      (node (ref "CAN") (pin "2") (pinfunction "2_2") (pintype "passive"))
      (node (ref "R8") (pin "1") (pinfunction "1_1") (pintype "passive"))
      (node (ref "U4") (pin "7") (pinfunction "CANH_7") (pintype "passive"))
    )
    (net (code "8") (name "/CANL") (class "Default")
      (node (ref "CAN") (pin "3") (pinfunction "3_3") (pintype "passive"))
      (node (ref "R8") (pin "2") (pinfunction "2_2") (pintype "passive"))
      (node (ref "U4") (pin "6") (pinfunction "CANL_6") (pintype "passive"))
    )
    (net (code "9") (name "/EEPROM_SCL") (class "Default")
      (node (ref "IIC1") (pin "3") (pinfunction "3_3") (pintype "passive"))
      (node (ref "R9") (pin "1") (pinfunction "1_1") (pintype "passive"))
      (node (ref "U17") (pin "23") (pinfunction "SCL_23") (pintype "passive"))
      (node (ref "U5") (pin "35") (pinfunction "PF6_35") (pintype "passive"))
      (node (ref "U6") (pin "6") (pinfunction "SCL_6") (pintype "passive"))
    )
    (net (code "10") (name "/EEPROM_SDA") (class "Default")
      (node (ref "IIC1") (pin "4") (pinfunction "4_4") (pintype "passive"))
      (node (ref "R10") (pin "1") (pinfunction "1_1") (pintype "passive"))
      (node (ref "U17") (pin "24") (pinfunction "SDA_24") (pintype "passive"))
      (node (ref "U5") (pin "36") (pinfunction "PF7_36") (pintype "passive"))
      (node (ref "U6") (pin "5") (pinfunction "SDA_5") (pintype "passive"))
    )
    (net (code "11") (name "/FB") (class "Default")
      (node (ref "C1") (pin "2") (pinfunction "2_2") (pintype "passive"))
      (node (ref "R1") (pin "1") (pinfunction "1_1") (pintype "passive"))
      (node (ref "R2") (pin "2") (pinfunction "2_2") (pintype "passive"))
      (node (ref "U3") (pin "3") (pinfunction "FB_3") (pintype "passive"))
    )
    (net (code "12") (name "/M0_HO1") (class "Default")
      (node (ref "D4") (pin "1") (pinfunction "K_1") (pintype "passive"))
      (node (ref "R15") (pin "1") (pinfunction "1_1") (pintype "passive"))
      (node (ref "U7") (pin "19") (pinfunction "HO1_19") (pintype "passive"))
    )
    (net (code "13") (name "/M0_HO1_1") (class "Default")
      (node (ref "D14") (pin "1") (pinfunction "K_1") (pintype "passive"))
      (node (ref "R32") (pin "1") (pinfunction "1_1") (pintype "passive"))
      (node (ref "U11") (pin "19") (pinfunction "HO1_19") (pintype "passive"))
    )
    (net (code "14") (name "/M0_HO2") (class "Default")
      (node (ref "D5") (pin "1") (pinfunction "K_1") (pintype "passive"))
      (node (ref "R16") (pin "1") (pinfunction "1_1") (pintype "passive"))
      (node (ref "U7") (pin "16") (pinfunction "HO2_16") (pintype "passive"))
    )
    (net (code "15") (name "/M0_HO2_1") (class "Default")
      (node (ref "D16") (pin "1") (pinfunction "K_1") (pintype "passive"))
      (node (ref "R34") (pin "1") (pinfunction "1_1") (pintype "passive"))
      (node (ref "U11") (pin "16") (pinfunction "HO2_16") (pintype "passive"))
    )
    (net (code "16") (name "/M0_HO3") (class "Default")
      (node (ref "D6") (pin "1") (pinfunction "K_1") (pintype "passive"))
      (node (ref "R17") (pin "1") (pinfunction "1_1") (pintype "passive"))
      (node (ref "U7") (pin "13") (pinfunction "HO3_13") (pintype "passive"))
    )
    (net (code "17") (name "/M0_HO3_1") (class "Default")
      (node (ref "D18") (pin "1") (pinfunction "K_1") (pintype "passive"))
      (node (ref "R36") (pin "1") (pinfunction "1_1") (pintype "passive"))
      (node (ref "U11") (pin "13") (pinfunction "HO3_13") (pintype "passive"))
    )
    (net (code "18") (name "/M0_IN1") (class "Default")
      (node (ref "R12") (pin "2") (pinfunction "2_2") (pintype "passive"))
      (node (ref "U7") (pin "1") (pinfunction "HIN1_1") (pintype "passive"))
      (node (ref "U7") (pin "4") (pinfunction "LIN1#_4") (pintype "passive"))
    )
    (net (code "19") (name "/M0_IN1_1") (class "Default")
      (node (ref "R42") (pin "2") (pinfunction "2_2") (pintype "passive"))
      (node (ref "U11") (pin "1") (pinfunction "HIN1_1") (pintype "passive"))
      (node (ref "U11") (pin "4") (pinfunction "LIN1#_4") (pintype "passive"))
    )
    (net (code "20") (name "/M0_IN2") (class "Default")
      (node (ref "R13") (pin "2") (pinfunction "2_2") (pintype "passive"))
      (node (ref "U7") (pin "2") (pinfunction "HIN2_2") (pintype "passive"))
      (node (ref "U7") (pin "5") (pinfunction "LIN2#_5") (pintype "passive"))
    )
    (net (code "21") (name "/M0_IN2_1") (class "Default")
      (node (ref "R43") (pin "2") (pinfunction "2_2") (pintype "passive"))
      (node (ref "U11") (pin "2") (pinfunction "HIN2_2") (pintype "passive"))
      (node (ref "U11") (pin "5") (pinfunction "LIN2#_5") (pintype "passive"))
    )
    (net (code "22") (name "/M0_IN3") (class "Default")
      (node (ref "R14") (pin "2") (pinfunction "2_2") (pintype "passive"))
      (node (ref "U7") (pin "3") (pinfunction "HIN3_3") (pintype "passive"))
      (node (ref "U7") (pin "6") (pinfunction "LIN3#_6") (pintype "passive"))
    )
    (net (code "23") (name "/M0_IN3_1") (class "Default")
      (node (ref "R44") (pin "2") (pinfunction "2_2") (pintype "passive"))
      (node (ref "U11") (pin "3") (pinfunction "HIN3_3") (pintype "passive"))
      (node (ref "U11") (pin "6") (pinfunction "LIN3#_6") (pintype "passive"))
    )
    (net (code "24") (name "/M0_IN_IU") (class "Default")
      (node (ref "Q4") (pin "3") (pinfunction "S_3") (pintype "passive"))
      (node (ref "R21") (pin "2") (pinfunction "2_2") (pintype "passive"))
      (node (ref "U8") (pin "4") (pinfunction "IN+_4") (pintype "passive"))
    )
    (net (code "25") (name "/M0_IN_IU_1") (class "Default")
      (node (ref "Q8") (pin "3") (pinfunction "S_3") (pintype "passive"))
      (node (ref "R40") (pin "2") (pinfunction "2_2") (pintype "passive"))
      (node (ref "U12") (pin "4") (pinfunction "IN+_4") (pintype "passive"))
    )
    (net (code "26") (name "/M0_IN_IV") (class "Default")
      (node (ref "Q5") (pin "3") (pinfunction "S_3") (pintype "passive"))
      (node (ref "R22") (pin "2") (pinfunction "2_2") (pintype "passive"))
      (node (ref "U9") (pin "4") (pinfunction "IN+_4") (pintype "passive"))
    )
    (net (code "27") (name "/M0_IN_IV_1") (class "Default")
      (node (ref "Q10") (pin "3") (pinfunction "S_3") (pintype "passive"))
      (node (ref "R41") (pin "2") (pinfunction "2_2") (pintype "passive"))
      (node (ref "U13") (pin "4") (pinfunction "IN+_4") (pintype "passive"))
    )
    (net (code "28") (name "/M0_IU") (class "Default")
      (node (ref "U5") (pin "14") (pinfunction "PA4_14") (pintype "passive"))
      (node (ref "U8") (pin "6") (pinfunction "OUT_6") (pintype "passive"))
    )
    (net (code "29") (name "/M0_IU_1") (class "Default")
      (node (ref "U12") (pin "6") (pinfunction "OUT_6") (pintype "passive"))
      (node (ref "U5") (pin "16") (pinfunction "PA6_16") (pintype "passive"))
    )
    (net (code "30") (name "/M0_IV") (class "Default")
      (node (ref "U5") (pin "15") (pinfunction "PA5_15") (pintype "passive"))
      (node (ref "U9") (pin "6") (pinfunction "OUT_6") (pintype "passive"))
    )
    (net (code "31") (name "/M0_IV_1") (class "Default")
      (node (ref "U13") (pin "6") (pinfunction "OUT_6") (pintype "passive"))
      (node (ref "U5") (pin "17") (pinfunction "PA7_17") (pintype "passive"))
    )
    (net (code "32") (name "/M0_LO1") (class "Default")
      (node (ref "D7") (pin "1") (pinfunction "K_1") (pintype "passive"))
      (node (ref "R18") (pin "1") (pinfunction "1_1") (pintype "passive"))
      (node (ref "U7") (pin "11") (pinfunction "LO1_11") (pintype "passive"))
    )
    (net (code "33") (name "/M0_LO1_1") (class "Default")
      (node (ref "D15") (pin "1") (pinfunction "K_1") (pintype "passive"))
      (node (ref "R33") (pin "1") (pinfunction "1_1") (pintype "passive"))
      (node (ref "U11") (pin "11") (pinfunction "LO1_11") (pintype "passive"))
    )
    (net (code "34") (name "/M0_LO2") (class "Default")
      (node (ref "D8") (pin "1") (pinfunction "K_1") (pintype "passive"))
      (node (ref "R19") (pin "1") (pinfunction "1_1") (pintype "passive"))
      (node (ref "U7") (pin "10") (pinfunction "LO2_10") (pintype "passive"))
    )
    (net (code "35") (name "/M0_LO2_1") (class "Default")
      (node (ref "D17") (pin "1") (pinfunction "K_1") (pintype "passive"))
      (node (ref "R35") (pin "1") (pinfunction "1_1") (pintype "passive"))
      (node (ref "U11") (pin "10") (pinfunction "LO2_10") (pintype "passive"))
    )
    (net (code "36") (name "/M0_LO3") (class "Default")
      (node (ref "D9") (pin "1") (pinfunction "K_1") (pintype "passive"))
      (node (ref "R20") (pin "1") (pinfunction "1_1") (pintype "passive"))
      (node (ref "U7") (pin "9") (pinfunction "LO3_9") (pintype "passive"))
    )
    (net (code "37") (name "/M0_LO3_1") (class "Default")
      (node (ref "D19") (pin "1") (pinfunction "K_1") (pintype "passive"))
      (node (ref "R37") (pin "1") (pinfunction "1_1") (pintype "passive"))
      (node (ref "U11") (pin "9") (pinfunction "LO3_9") (pintype "passive"))
    )
    (net (code "38") (name "/M0_UOUT") (class "Default")
      (node (ref "C18") (pin "1") (pinfunction "1_1") (pintype "passive"))
      (node (ref "Q1") (pin "3") (pinfunction "S_3") (pintype "passive"))
      (node (ref "Q4") (pin "2") (pinfunction "D_2") (pintype "passive"))
      (node (ref "U2") (pin "1") (pinfunction "1_1") (pintype "passive"))
      (node (ref "U7") (pin "18") (pinfunction "VS1_18") (pintype "passive"))
    )
    (net (code "39") (name "/M0_UOUT_1") (class "Default")
      (node (ref "C31") (pin "1") (pinfunction "1_1") (pintype "passive"))
      (node (ref "Q7") (pin "3") (pinfunction "S_3") (pintype "passive"))
      (node (ref "Q8") (pin "2") (pinfunction "D_2") (pintype "passive"))
      (node (ref "U1") (pin "1") (pinfunction "1_1") (pintype "passive"))
      (node (ref "U11") (pin "18") (pinfunction "VS1_18") (pintype "passive"))
    )
    (net (code "40") (name "/M0_VB1") (class "Default")
      (node (ref "C18") (pin "2") (pinfunction "2_2") (pintype "passive"))
      (node (ref "D1") (pin "1") (pinfunction "K_1") (pintype "passive"))
      (node (ref "U7") (pin "20") (pinfunction "VB1_20") (pintype "passive"))
    )
    (net (code "41") (name "/M0_VB1_1") (class "Default")
      (node (ref "C31") (pin "2") (pinfunction "2_2") (pintype "passive"))
      (node (ref "D11") (pin "1") (pinfunction "K_1") (pintype "passive"))
      (node (ref "U11") (pin "20") (pinfunction "VB1_20") (pintype "passive"))
    )
    (net (code "42") (name "/M0_VB2") (class "Default")
      (node (ref "C19") (pin "2") (pinfunction "2_2") (pintype "passive"))
      (node (ref "D2") (pin "1") (pinfunction "K_1") (pintype "passive"))
      (node (ref "U7") (pin "17") (pinfunction "VB2_17") (pintype "passive"))
    )
    (net (code "43") (name "/M0_VB2_1") (class "Default")
      (node (ref "C32") (pin "2") (pinfunction "2_2") (pintype "passive"))
      (node (ref "D12") (pin "1") (pinfunction "K_1") (pintype "passive"))
      (node (ref "U11") (pin "17") (pinfunction "VB2_17") (pintype "passive"))
    )
    (net (code "44") (name "/M0_VB3") (class "Default")
      (node (ref "C20") (pin "2") (pinfunction "2_2") (pintype "passive"))
      (node (ref "D3") (pin "1") (pinfunction "K_1") (pintype "passive"))
      (node (ref "U7") (pin "14") (pinfunction "VB3_14") (pintype "passive"))
    )
    (net (code "45") (name "/M0_VB3_1") (class "Default")
      (node (ref "C30") (pin "2") (pinfunction "2_2") (pintype "passive"))
      (node (ref "D13") (pin "1") (pinfunction "K_1") (pintype "passive"))
      (node (ref "U11") (pin "14") (pinfunction "VB3_14") (pintype "passive"))
    )
    (net (code "46") (name "/M0_VOUT") (class "Default")
      (node (ref "C19") (pin "1") (pinfunction "1_1") (pintype "passive"))
      (node (ref "Q2") (pin "3") (pinfunction "S_3") (pintype "passive"))
      (node (ref "Q5") (pin "2") (pinfunction "D_2") (pintype "passive"))
      (node (ref "U7") (pin "15") (pinfunction "VS2_15") (pintype "passive"))
      (node (ref "V2") (pin "1") (pinfunction "1_1") (pintype "passive"))
    )
    (net (code "47") (name "/M0_VOUT_1") (class "Default")
      (node (ref "C32") (pin "1") (pinfunction "1_1") (pintype "passive"))
      (node (ref "Q10") (pin "2") (pinfunction "D_2") (pintype "passive"))
      (node (ref "Q9") (pin "3") (pinfunction "S_3") (pintype "passive"))
      (node (ref "U11") (pin "15") (pinfunction "VS2_15") (pintype "passive"))
      (node (ref "V1") (pin "1") (pinfunction "1_1") (pintype "passive"))
    )
    (net (code "48") (name "/M0_VS3") (class "Default")
      (node (ref "C20") (pin "1") (pinfunction "1_1") (pintype "passive"))
      (node (ref "Q3") (pin "3") (pinfunction "S_3") (pintype "passive"))
      (node (ref "Q6") (pin "2") (pinfunction "D_2") (pintype "passive"))
      (node (ref "U7") (pin "12") (pinfunction "VS3_12") (pintype "passive"))
      (node (ref "W2") (pin "1") (pinfunction "1_1") (pintype "passive"))
    )
    (net (code "49") (name "/M0_VS3_1") (class "Default")
      (node (ref "C30") (pin "1") (pinfunction "1_1") (pintype "passive"))
      (node (ref "Q11") (pin "3") (pinfunction "S_3") (pintype "passive"))
      (node (ref "Q12") (pin "2") (pinfunction "D_2") (pintype "passive"))
      (node (ref "U11") (pin "12") (pinfunction "VS3_12") (pintype "passive"))
      (node (ref "W1") (pin "1") (pinfunction "1_1") (pintype "passive"))
    )
    (net (code "50") (name "/NRST") (class "Default")
      (node (ref "C11") (pin "2") (pinfunction "2_2") (pintype "passive"))
      (node (ref "NRST") (pin "1") (pinfunction "1_1") (pintype "passive"))
      (node (ref "U5") (pin "7") (pinfunction "NRST_7") (pintype "passive"))
    )
    (net (code "51") (name "/OSC_IN") (class "Default")
      (node (ref "C14") (pin "2") (pinfunction "2_2") (pintype "passive"))
      (node (ref "U5") (pin "5") (pinfunction "PD0/OSC_IN_5") (pintype "passive"))
      (node (ref "X2") (pin "1") (pinfunction "1_1") (pintype "passive"))
    )
    (net (code "52") (name "/OSC_OUT") (class "Default")
      (node (ref "C12") (pin "1") (pinfunction "1_1") (pintype "passive"))
      (node (ref "U5") (pin "6") (pinfunction "PD1/OSC_OUT_6") (pintype "passive"))
      (node (ref "X2") (pin "3") (pinfunction "3_3") (pintype "passive"))
    )
    (net (code "53") (name "/PA0") (class "Default")
      (node (ref "KEY1") (pin "1") (pinfunction "1_1") (pintype "passive"))
      (node (ref "KEY2") (pin "1") (pinfunction "1_1") (pintype "passive"))
      (node (ref "KEY3") (pin "1") (pinfunction "1_1") (pintype "passive"))
      (node (ref "U5") (pin "10") (pinfunction "PA0/WKUP_10") (pintype "passive"))
    )
    (net (code "54") (name "/PA1") (class "Default")
      (node (ref "R14") (pin "1") (pinfunction "1_1") (pintype "passive"))
      (node (ref "U5") (pin "11") (pinfunction "PA1_11") (pintype "passive"))
    )
    (net (code "55") (name "/PA2") (class "Default")
      (node (ref "R13") (pin "1") (pinfunction "1_1") (pintype "passive"))
      (node (ref "U5") (pin "12") (pinfunction "PA2_12") (pintype "passive"))
    )
    (net (code "56") (name "/PA3") (class "Default")
      (node (ref "R12") (pin "1") (pinfunction "1_1") (pintype "passive"))
      (node (ref "U5") (pin "13") (pinfunction "PA3_13") (pintype "passive"))
    )
    (net (code "57") (name "/PA8") (class "Default")
      (node (ref "R44") (pin "1") (pinfunction "1_1") (pintype "passive"))
      (node (ref "U5") (pin "29") (pinfunction "PA8_29") (pintype "passive"))
    )
    (net (code "58") (name "/PA9") (class "Default")
      (node (ref "R43") (pin "1") (pinfunction "1_1") (pintype "passive"))
      (node (ref "U5") (pin "30") (pinfunction "PA9_30") (pintype "passive"))
    )
    (net (code "59") (name "/PA10") (class "Default")
      (node (ref "R42") (pin "1") (pinfunction "1_1") (pintype "passive"))
      (node (ref "U5") (pin "31") (pinfunction "PA10_31") (pintype "passive"))
    )
    (net (code "60") (name "/PA13") (class "Default")
      (node (ref "SWD") (pin "3") (pinfunction "3_3") (pintype "passive"))
      (node (ref "U5") (pin "34") (pinfunction "PA13_34") (pintype "passive"))
    )
    (net (code "61") (name "/PA14") (class "Default")
      (node (ref "SWD") (pin "4") (pinfunction "4_4") (pintype "passive"))
      (node (ref "U5") (pin "37") (pinfunction "PA14_37") (pintype "passive"))
    )
    (net (code "62") (name "/PB1") (class "Default")
      (node (ref "LED2") (pin "1") (pinfunction "K_1") (pintype "passive"))
      (node (ref "U5") (pin "19") (pinfunction "PB1_19") (pintype "passive"))
    )
    (net (code "63") (name "/PB6") (class "Default")
      (node (ref "U5") (pin "42") (pinfunction "PB6_42") (pintype "passive"))
      (node (ref "USART1") (pin "3") (pinfunction "3_3") (pintype "passive"))
    )
    (net (code "64") (name "/PB7") (class "Default")
      (node (ref "U5") (pin "43") (pinfunction "PB7_43") (pintype "passive"))
      (node (ref "USART1") (pin "4") (pinfunction "4_4") (pintype "passive"))
    )
    (net (code "65") (name "/PB10") (class "Default")
      (node (ref "IIC2") (pin "3") (pinfunction "3_3") (pintype "passive"))
      (node (ref "R47") (pin "1") (pinfunction "1_1") (pintype "passive"))
      (node (ref "U16") (pin "3") (pinfunction "SCL_3") (pintype "passive"))
      (node (ref "U5") (pin "21") (pinfunction "PB10_21") (pintype "passive"))
    )
    (net (code "66") (name "/PB11") (class "Default")
      (node (ref "IIC2") (pin "4") (pinfunction "4_4") (pintype "passive"))
      (node (ref "R48") (pin "1") (pinfunction "1_1") (pintype "passive"))
      (node (ref "U16") (pin "4") (pinfunction "SDA_4") (pintype "passive"))
      (node (ref "U5") (pin "22") (pinfunction "PB11_22") (pintype "passive"))
    )
    (net (code "67") (name "/SW") (class "Default")
      (node (ref "C2") (pin "2") (pinfunction "2_2") (pintype "passive"))
      (node (ref "L1") (pin "1") (pinfunction "1_1") (pintype "passive"))
      (node (ref "U3") (pin "6") (pinfunction "SW_6") (pintype "passive"))
    )
    (net (code "68") (name "/VREF") (class "Default")
      (node (ref "R23") (pin "2") (pinfunction "2_2") (pintype "passive"))
      (node (ref "R24") (pin "1") (pinfunction "1_1") (pintype "passive"))
      (node (ref "U8") (pin "1") (pinfunction "REF_1") (pintype "passive"))
      (node (ref "U9") (pin "1") (pinfunction "REF_1") (pintype "passive"))
    )
    (net (code "69") (name "/VREF_1") (class "Default")
      (node (ref "R38") (pin "2") (pinfunction "2_2") (pintype "passive"))
      (node (ref "R39") (pin "1") (pinfunction "1_1") (pintype "passive"))
      (node (ref "U12") (pin "1") (pinfunction "REF_1") (pintype "passive"))
      (node (ref "U13") (pin "1") (pinfunction "REF_1") (pintype "passive"))
    )
    (net (code "70") (name "3V3") (class "Default")
      (node (ref "BOOT0") (pin "2") (pinfunction "2_2") (pintype "passive"))
      (node (ref "C1") (pin "1") (pinfunction "1_1") (pintype "passive"))
      (node (ref "C15") (pin "1") (pinfunction "1_1") (pintype "passive"))
      (node (ref "C16") (pin "2") (pinfunction "2_2") (pintype "passive"))
      (node (ref "C17") (pin "2") (pinfunction "2_2") (pintype "passive"))
      (node (ref "C23") (pin "1") (pinfunction "1_1") (pintype "passive"))
      (node (ref "C24") (pin "1") (pinfunction "1_1") (pintype "passive"))
      (node (ref "C25") (pin "2") (pinfunction "2_2") (pintype "passive"))
      (node (ref "C28") (pin "1") (pinfunction "1_1") (pintype "passive"))
      (node (ref "C29") (pin "1") (pinfunction "1_1") (pintype "passive"))
      (node (ref "C3") (pin "2") (pinfunction "2_2") (pintype "passive"))
      (node (ref "C4") (pin "2") (pinfunction "2_2") (pintype "passive"))
      (node (ref "C44") (pin "1") (pinfunction "1_1") (pintype "passive"))
      (node (ref "C45") (pin "2") (pinfunction "2_2") (pintype "passive"))
      (node (ref "C6") (pin "2") (pinfunction "2_2") (pintype "passive"))
      (node (ref "C7") (pin "2") (pinfunction "2_2") (pintype "passive"))
      (node (ref "C8") (pin "2") (pinfunction "2_2") (pintype "passive"))
      (node (ref "IIC1") (pin "2") (pinfunction "2_2") (pintype "passive"))
      (node (ref "IIC2") (pin "2") (pinfunction "2_2") (pintype "passive"))
      (node (ref "L1") (pin "2") (pinfunction "2_2") (pintype "passive"))
      (node (ref "L2") (pin "2") (pinfunction "2_2") (pintype "passive"))
      (node (ref "R10") (pin "2") (pinfunction "2_2") (pintype "passive"))
      (node (ref "R11") (pin "1") (pinfunction "1_1") (pintype "passive"))
      (node (ref "R2") (pin "1") (pinfunction "1_1") (pintype "passive"))
      (node (ref "R23") (pin "1") (pinfunction "1_1") (pintype "passive"))
      (node (ref "R25") (pin "1") (pinfunction "1_1") (pintype "passive"))
      (node (ref "R31") (pin "2") (pinfunction "2_2") (pintype "passive"))
      (node (ref "R38") (pin "1") (pinfunction "1_1") (pintype "passive"))
      (node (ref "R47") (pin "2") (pinfunction "2_2") (pintype "passive"))
      (node (ref "R48") (pin "2") (pinfunction "2_2") (pintype "passive"))
      (node (ref "R9") (pin "2") (pinfunction "2_2") (pintype "passive"))
      (node (ref "SWD") (pin "2") (pinfunction "2_2") (pintype "passive"))
      (node (ref "U12") (pin "3") (pinfunction "V+_3") (pintype "passive"))
      (node (ref "U13") (pin "3") (pinfunction "V+_3") (pintype "passive"))
      (node (ref "U16") (pin "2") (pinfunction "VCC_2") (pintype "passive"))
      (node (ref "U17") (pin "13") (pinfunction "VDD_13") (pintype "passive"))
      (node (ref "U17") (pin "8") (pinfunction "VLOGIC_8") (pintype "passive"))
      (node (ref "U4") (pin "3") (pinfunction "VCC_3") (pintype "passive"))
      (node (ref "U5") (pin "1") (pinfunction "VBAT_1") (pintype "passive"))
      (node (ref "U5") (pin "24") (pinfunction "VDD_24") (pintype "passive"))
      (node (ref "U5") (pin "48") (pinfunction "VDD_48") (pintype "passive"))
      (node (ref "U6") (pin "8") (pinfunction "VCC_8") (pintype "passive"))
      (node (ref "U8") (pin "3") (pinfunction "V+_3") (pintype "passive"))
      (node (ref "U9") (pin "3") (pinfunction "V+_3") (pintype "passive"))
      (node (ref "USART1") (pin "2") (pinfunction "2_2") (pintype "passive"))
    )
    (net (code "71") (name "GND") (class "Default")
      (node (ref "C10") (pin "1") (pinfunction "1_1") (pintype "passive"))
      (node (ref "C11") (pin "1") (pinfunction "1_1") (pintype "passive"))
      (node (ref "C12") (pin "2") (pinfunction "2_2") (pintype "passive"))
      (node (ref "C13") (pin "2") (pinfunction "2_2") (pintype "passive"))
      (node (ref "C14") (pin "1") (pinfunction "1_1") (pintype "passive"))
      (node (ref "C15") (pin "2") (pinfunction "2_2") (pintype "passive"))
      (node (ref "C16") (pin "1") (pinfunction "1_1") (pintype "passive"))
      (node (ref "C17") (pin "1") (pinfunction "1_1") (pintype "passive"))
      (node (ref "C21") (pin "1") (pinfunction "1_1") (pintype "passive"))
      (node (ref "C22") (pin "1") (pinfunction "1_1") (pintype "passive"))
      (node (ref "C23") (pin "2") (pinfunction "2_2") (pintype "passive"))
      (node (ref "C24") (pin "2") (pinfunction "2_2") (pintype "passive"))
      (node (ref "C25") (pin "1") (pinfunction "1_1") (pintype "passive"))
      (node (ref "C26") (pin "1") (pinfunction "1_1") (pintype "passive"))
      (node (ref "C27") (pin "1") (pinfunction "1_1") (pintype "passive"))
      (node (ref "C28") (pin "2") (pinfunction "2_2") (pintype "passive"))
      (node (ref "C29") (pin "2") (pinfunction "2_2") (pintype "passive"))
      (node (ref "C3") (pin "1") (pinfunction "1_1") (pintype "passive"))
      (node (ref "C33") (pin "2") (pinfunction "2_2") (pintype "passive"))
      (node (ref "C34") (pin "2") (pinfunction "2_2") (pintype "passive"))
      (node (ref "C35") (pin "2") (pinfunction "2_2") (pintype "passive"))
      (node (ref "C36") (pin "2") (pinfunction "2_2") (pintype "passive"))
      (node (ref "C37") (pin "2") (pinfunction "2_2") (pintype "passive"))
      (node (ref "C38") (pin "2") (pinfunction "2_2") (pintype "passive"))
      (node (ref "C39") (pin "2") (pinfunction "2_2") (pintype "passive"))
      (node (ref "C4") (pin "1") (pinfunction "1_1") (pintype "passive"))
      (node (ref "C40") (pin "2") (pinfunction "2_2") (pintype "passive"))
      (node (ref "C41") (pin "1") (pinfunction "1_1") (pintype "passive"))
      (node (ref "C42") (pin "2") (pinfunction "2_2") (pintype "passive"))
      (node (ref "C43") (pin "1") (pinfunction "1_1") (pintype "passive"))
      (node (ref "C44") (pin "2") (pinfunction "2_2") (pintype "passive"))
      (node (ref "C45") (pin "1") (pinfunction "1_1") (pintype "passive"))
      (node (ref "C5") (pin "2") (pinfunction "2_2") (pintype "passive"))
      (node (ref "C6") (pin "1") (pinfunction "1_1") (pintype "passive"))
      (node (ref "C7") (pin "1") (pinfunction "1_1") (pintype "passive"))
      (node (ref "C8") (pin "1") (pinfunction "1_1") (pintype "passive"))
      (node (ref "C9") (pin "1") (pinfunction "1_1") (pintype "passive"))
      (node (ref "CAN") (pin "1") (pinfunction "1_1") (pintype "passive"))
      (node (ref "CAN") (pin "4") (pinfunction "4_4") (pintype "passive"))
      (node (ref "CAN") (pin "5") (pinfunction "5_5") (pintype "passive"))
      (node (ref "D10") (pin "1") (pinfunction "1_1") (pintype "passive"))
      (node (ref "IIC1") (pin "1") (pinfunction "1_1") (pintype "passive"))
      (node (ref "IIC1") (pin "5") (pinfunction "5_5") (pintype "passive"))
      (node (ref "IIC1") (pin "6") (pinfunction "6_6") (pintype "passive"))
      (node (ref "IIC2") (pin "1") (pinfunction "1_1") (pintype "passive"))
      (node (ref "IIC2") (pin "5") (pinfunction "5_5") (pintype "passive"))
      (node (ref "IIC2") (pin "6") (pinfunction "6_6") (pintype "passive"))
      (node (ref "LED1") (pin "1") (pinfunction "K_1") (pintype "passive"))
      (node (ref "NRST") (pin "2") (pinfunction "2_2") (pintype "passive"))
      (node (ref "Q12") (pin "3") (pinfunction "S_3") (pintype "passive"))
      (node (ref "Q6") (pin "3") (pinfunction "S_3") (pintype "passive"))
      (node (ref "R1") (pin "2") (pinfunction "2_2") (pintype "passive"))
      (node (ref "R21") (pin "1") (pinfunction "1_1") (pintype "passive"))
      (node (ref "R22") (pin "1") (pinfunction "1_1") (pintype "passive"))
      (node (ref "R24") (pin "2") (pinfunction "2_2") (pintype "passive"))
      (node (ref "R30") (pin "1") (pinfunction "1_1") (pintype "passive"))
      (node (ref "R39") (pin "2") (pinfunction "2_2") (pintype "passive"))
      (node (ref "R4") (pin "1") (pinfunction "1_1") (pintype "passive"))
      (node (ref "R40") (pin "1") (pinfunction "1_1") (pintype "passive"))
      (node (ref "R41") (pin "1") (pinfunction "1_1") (pintype "passive"))
      (node (ref "R50") (pin "2") (pinfunction "2_2") (pintype "passive"))
      (node (ref "R6") (pin "1") (pinfunction "1_1") (pintype "passive"))
      (node (ref "SWD") (pin "1") (pinfunction "1_1") (pintype "passive"))
      (node (ref "SWD") (pin "5") (pinfunction "5_5") (pintype "passive"))
      (node (ref "SWD") (pin "6") (pinfunction "6_6") (pintype "passive"))
      (node (ref "U11") (pin "8") (pinfunction "GND_8") (pintype "passive"))
      (node (ref "U12") (pin "2") (pinfunction "GND_2") (pintype "passive"))
      (node (ref "U12") (pin "5") (pinfunction "IN-_5") (pintype "passive"))
      (node (ref "U13") (pin "2") (pinfunction "GND_2") (pintype "passive"))
      (node (ref "U13") (pin "5") (pinfunction "IN-_5") (pintype "passive"))
      (node (ref "U15") (pin "2") (pinfunction "-_2") (pintype "passive"))
      (node (ref "U16") (pin "1") (pinfunction "GND_1") (pintype "passive"))
      (node (ref "U17") (pin "1") (pinfunction "CLKIN_1") (pintype "passive"))
      (node (ref "U17") (pin "11") (pinfunction "FSYNC_11") (pintype "passive"))
      (node (ref "U17") (pin "18") (pinfunction "GND_18") (pintype "passive"))
      (node (ref "U17") (pin "25") (pinfunction "EP_25") (pintype "passive"))
      (node (ref "U17") (pin "9") (pinfunction "AD0_9") (pintype "passive"))
      (node (ref "U3") (pin "2") (pinfunction "GND_2") (pintype "passive"))
      (node (ref "U4") (pin "2") (pinfunction "GND_2") (pintype "passive"))
      (node (ref "U4") (pin "8") (pinfunction "RS_8") (pintype "passive"))
      (node (ref "U5") (pin "23") (pinfunction "VSS_23") (pintype "passive"))
      (node (ref "U5") (pin "47") (pinfunction "VSS_47") (pintype "passive"))
      (node (ref "U5") (pin "8") (pinfunction "VSSA_8") (pintype "passive"))
      (node (ref "U6") (pin "1") (pinfunction "A0_1") (pintype "passive"))
      (node (ref "U6") (pin "2") (pinfunction "A1_2") (pintype "passive"))
      (node (ref "U6") (pin "3") (pinfunction "A2_3") (pintype "passive"))
      (node (ref "U6") (pin "4") (pinfunction "GND_4") (pintype "passive"))
      (node (ref "U6") (pin "7") (pinfunction "WP_7") (pintype "passive"))
      (node (ref "U7") (pin "8") (pinfunction "GND_8") (pintype "passive"))
      (node (ref "U8") (pin "2") (pinfunction "GND_2") (pintype "passive"))
      (node (ref "U8") (pin "5") (pinfunction "IN-_5") (pintype "passive"))
      (node (ref "U9") (pin "2") (pinfunction "GND_2") (pintype "passive"))
      (node (ref "U9") (pin "5") (pinfunction "IN-_5") (pintype "passive"))
      (node (ref "USART1") (pin "1") (pinfunction "1_1") (pintype "passive"))
      (node (ref "USART1") (pin "5") (pinfunction "5_5") (pintype "passive"))
      (node (ref "USART1") (pin "6") (pinfunction "6_6") (pintype "passive"))
      (node (ref "X2") (pin "2") (pinfunction "2_2") (pintype "passive"))
    )
    (net (code "72") (name "Net-(D4-A)") (class "Default")
      (node (ref "D4") (pin "2") (pinfunction "A_2") (pintype "passive"))
      (node (ref "Q1") (pin "1") (pinfunction "G_1") (pintype "passive"))
      (node (ref "R15") (pin "2") (pinfunction "2_2") (pintype "passive"))
    )
    (net (code "73") (name "Net-(D5-A)") (class "Default")
      (node (ref "D5") (pin "2") (pinfunction "A_2") (pintype "passive"))
      (node (ref "Q2") (pin "1") (pinfunction "G_1") (pintype "passive"))
      (node (ref "R16") (pin "2") (pinfunction "2_2") (pintype "passive"))
    )
    (net (code "74") (name "Net-(D6-A)") (class "Default")
      (node (ref "D6") (pin "2") (pinfunction "A_2") (pintype "passive"))
      (node (ref "Q3") (pin "1") (pinfunction "G_1") (pintype "passive"))
      (node (ref "R17") (pin "2") (pinfunction "2_2") (pintype "passive"))
    )
    (net (code "75") (name "Net-(D7-A)") (class "Default")
      (node (ref "D7") (pin "2") (pinfunction "A_2") (pintype "passive"))
      (node (ref "Q4") (pin "1") (pinfunction "G_1") (pintype "passive"))
      (node (ref "R18") (pin "2") (pinfunction "2_2") (pintype "passive"))
    )
    (net (code "76") (name "Net-(D8-A)") (class "Default")
      (node (ref "D8") (pin "2") (pinfunction "A_2") (pintype "passive"))
      (node (ref "Q5") (pin "1") (pinfunction "G_1") (pintype "passive"))
      (node (ref "R19") (pin "2") (pinfunction "2_2") (pintype "passive"))
    )
    (net (code "77") (name "Net-(D9-A)") (class "Default")
      (node (ref "D9") (pin "2") (pinfunction "A_2") (pintype "passive"))
      (node (ref "Q6") (pin "1") (pinfunction "G_1") (pintype "passive"))
      (node (ref "R20") (pin "2") (pinfunction "2_2") (pintype "passive"))
    )
    (net (code "78") (name "Net-(D14-A)") (class "Default")
      (node (ref "D14") (pin "2") (pinfunction "A_2") (pintype "passive"))
      (node (ref "Q7") (pin "1") (pinfunction "G_1") (pintype "passive"))
      (node (ref "R32") (pin "2") (pinfunction "2_2") (pintype "passive"))
    )
    (net (code "79") (name "Net-(D15-A)") (class "Default")
      (node (ref "D15") (pin "2") (pinfunction "A_2") (pintype "passive"))
      (node (ref "Q8") (pin "1") (pinfunction "G_1") (pintype "passive"))
      (node (ref "R33") (pin "2") (pinfunction "2_2") (pintype "passive"))
    )
    (net (code "80") (name "Net-(D16-A)") (class "Default")
      (node (ref "D16") (pin "2") (pinfunction "A_2") (pintype "passive"))
      (node (ref "Q9") (pin "1") (pinfunction "G_1") (pintype "passive"))
      (node (ref "R34") (pin "2") (pinfunction "2_2") (pintype "passive"))
    )
    (net (code "81") (name "Net-(D17-A)") (class "Default")
      (node (ref "D17") (pin "2") (pinfunction "A_2") (pintype "passive"))
      (node (ref "Q10") (pin "1") (pinfunction "G_1") (pintype "passive"))
      (node (ref "R35") (pin "2") (pinfunction "2_2") (pintype "passive"))
    )
    (net (code "82") (name "Net-(D18-A)") (class "Default")
      (node (ref "D18") (pin "2") (pinfunction "A_2") (pintype "passive"))
      (node (ref "Q11") (pin "1") (pinfunction "G_1") (pintype "passive"))
      (node (ref "R36") (pin "2") (pinfunction "2_2") (pintype "passive"))
    )
    (net (code "83") (name "Net-(D19-A)") (class "Default")
      (node (ref "D19") (pin "2") (pinfunction "A_2") (pintype "passive"))
      (node (ref "Q12") (pin "1") (pinfunction "G_1") (pintype "passive"))
      (node (ref "R37") (pin "2") (pinfunction "2_2") (pintype "passive"))
    )
    (net (code "84") (name "Net-(KEY1-Pad2)") (class "Default")
      (node (ref "KEY1") (pin "2") (pinfunction "2_2") (pintype "passive"))
      (node (ref "R27") (pin "2") (pinfunction "2_2") (pintype "passive"))
      (node (ref "R31") (pin "1") (pinfunction "1_1") (pintype "passive"))
    )
    (net (code "85") (name "Net-(KEY2-Pad2)") (class "Default")
      (node (ref "KEY2") (pin "2") (pinfunction "2_2") (pintype "passive"))
      (node (ref "R27") (pin "1") (pinfunction "1_1") (pintype "passive"))
      (node (ref "R28") (pin "2") (pinfunction "2_2") (pintype "passive"))
    )
    (net (code "86") (name "Net-(KEY3-Pad2)") (class "Default")
      (node (ref "KEY3") (pin "2") (pinfunction "2_2") (pintype "passive"))
      (node (ref "R28") (pin "1") (pinfunction "1_1") (pintype "passive"))
      (node (ref "R30") (pin "2") (pinfunction "2_2") (pintype "passive"))
    )
    (net (code "87") (name "Net-(LED1-A)") (class "Default")
      (node (ref "LED1") (pin "2") (pinfunction "A_2") (pintype "passive"))
      (node (ref "R11") (pin "2") (pinfunction "2_2") (pintype "passive"))
    )
    (net (code "88") (name "Net-(LED2-A)") (class "Default")
      (node (ref "LED2") (pin "2") (pinfunction "A_2") (pintype "passive"))
      (node (ref "R25") (pin "2") (pinfunction "2_2") (pintype "passive"))
    )
    (net (code "89") (name "Net-(U17-CPOUT)") (class "Default")
      (node (ref "C43") (pin "2") (pinfunction "2_2") (pintype "passive"))
      (node (ref "U17") (pin "20") (pinfunction "CPOUT_20") (pintype "passive"))
    )
    (net (code "90") (name "Net-(U17-REGOUT)") (class "Default")
      (node (ref "C42") (pin "1") (pinfunction "1_1") (pintype "passive"))
      (node (ref "U17") (pin "10") (pinfunction "REGOUT_10") (pintype "passive"))
    )
    (net (code "91") (name "VDDA") (class "Default")
      (node (ref "C10") (pin "2") (pinfunction "2_2") (pintype "passive"))
      (node (ref "C9") (pin "2") (pinfunction "2_2") (pintype "passive"))
      (node (ref "L2") (pin "1") (pinfunction "1_1") (pintype "passive"))
      (node (ref "U5") (pin "9") (pinfunction "VDDA_9") (pintype "passive"))
    )
    (net (code "92") (name "VIN") (class "Default")
      (node (ref "C13") (pin "1") (pinfunction "1_1") (pintype "passive"))
      (node (ref "C21") (pin "2") (pinfunction "2_2") (pintype "passive"))
      (node (ref "C22") (pin "2") (pinfunction "2_2") (pintype "passive"))
      (node (ref "C26") (pin "2") (pinfunction "2_2") (pintype "passive"))
      (node (ref "C27") (pin "2") (pinfunction "2_2") (pintype "passive"))
      (node (ref "C33") (pin "1") (pinfunction "1_1") (pintype "passive"))
      (node (ref "C34") (pin "1") (pinfunction "1_1") (pintype "passive"))
      (node (ref "C35") (pin "1") (pinfunction "1_1") (pintype "passive"))
      (node (ref "C36") (pin "1") (pinfunction "1_1") (pintype "passive"))
      (node (ref "C37") (pin "1") (pinfunction "1_1") (pintype "passive"))
      (node (ref "C38") (pin "1") (pinfunction "1_1") (pintype "passive"))
      (node (ref "C39") (pin "1") (pinfunction "1_1") (pintype "passive"))
      (node (ref "C40") (pin "1") (pinfunction "1_1") (pintype "passive"))
      (node (ref "C5") (pin "1") (pinfunction "1_1") (pintype "passive"))
      (node (ref "D1") (pin "2") (pinfunction "A_2") (pintype "passive"))
      (node (ref "D10") (pin "2") (pinfunction "2_2") (pintype "passive"))
      (node (ref "D11") (pin "2") (pinfunction "A_2") (pintype "passive"))
      (node (ref "D12") (pin "2") (pinfunction "A_2") (pintype "passive"))
      (node (ref "D13") (pin "2") (pinfunction "A_2") (pintype "passive"))
      (node (ref "D2") (pin "2") (pinfunction "A_2") (pintype "passive"))
      (node (ref "D3") (pin "2") (pinfunction "A_2") (pintype "passive"))
      (node (ref "Q1") (pin "2") (pinfunction "D_2") (pintype "passive"))
      (node (ref "Q11") (pin "2") (pinfunction "D_2") (pintype "passive"))
      (node (ref "Q2") (pin "2") (pinfunction "D_2") (pintype "passive"))
      (node (ref "Q3") (pin "2") (pinfunction "D_2") (pintype "passive"))
      (node (ref "Q7") (pin "2") (pinfunction "D_2") (pintype "passive"))
      (node (ref "Q9") (pin "2") (pinfunction "D_2") (pintype "passive"))
      (node (ref "R3") (pin "2") (pinfunction "2_2") (pintype "passive"))
      (node (ref "R49") (pin "1") (pinfunction "1_1") (pintype "passive"))
      (node (ref "U11") (pin "7") (pinfunction "VCC_7") (pintype "passive"))
      (node (ref "U15") (pin "1") (pinfunction "+_1") (pintype "passive"))
      (node (ref "U3") (pin "5") (pinfunction "IN_5") (pintype "passive"))
      (node (ref "U7") (pin "7") (pinfunction "VCC_7") (pintype "passive"))
    )
    (net (code "93") (name "unconnected-(U4-VREF-Pad5)") (class "Default")
      (node (ref "U4") (pin "5") (pinfunction "VREF_5") (pintype "passive+no_connect"))
    )
    (net (code "94") (name "unconnected-(U5-PA11-Pad32)") (class "Default")
      (node (ref "U5") (pin "32") (pinfunction "PA11_32") (pintype "passive+no_connect"))
    )
    (net (code "95") (name "unconnected-(U5-PA12-Pad33)") (class "Default")
      (node (ref "U5") (pin "33") (pinfunction "PA12_33") (pintype "passive+no_connect"))
    )
    (net (code "96") (name "unconnected-(U5-PA15-Pad38)") (class "Default")
      (node (ref "U5") (pin "38") (pinfunction "PA15_38") (pintype "passive+no_connect"))
    )
    (net (code "97") (name "unconnected-(U5-PB2-Pad20)") (class "Default")
      (node (ref "U5") (pin "20") (pinfunction "PB2_20") (pintype "passive+no_connect"))
    )
    (net (code "98") (name "unconnected-(U5-PB3-Pad39)") (class "Default")
      (node (ref "U5") (pin "39") (pinfunction "PB3_39") (pintype "passive+no_connect"))
    )
    (net (code "99") (name "unconnected-(U5-PB4-Pad40)") (class "Default")
      (node (ref "U5") (pin "40") (pinfunction "PB4_40") (pintype "passive+no_connect"))
    )
    (net (code "100") (name "unconnected-(U5-PB5-Pad41)") (class "Default")
      (node (ref "U5") (pin "41") (pinfunction "PB5_41") (pintype "passive+no_connect"))
    )
    (net (code "101") (name "unconnected-(U5-PB12-Pad25)") (class "Default")
      (node (ref "U5") (pin "25") (pinfunction "PB12_25") (pintype "passive+no_connect"))
    )
    (net (code "102") (name "unconnected-(U5-PB13-Pad26)") (class "Default")
      (node (ref "U5") (pin "26") (pinfunction "PB13_26") (pintype "passive+no_connect"))
    )
    (net (code "103") (name "unconnected-(U5-PB14-Pad27)") (class "Default")
      (node (ref "U5") (pin "27") (pinfunction "PB14_27") (pintype "passive+no_connect"))
    )
    (net (code "104") (name "unconnected-(U5-PB15-Pad28)") (class "Default")
      (node (ref "U5") (pin "28") (pinfunction "PB15_28") (pintype "passive+no_connect"))
    )
    (net (code "105") (name "unconnected-(U5-PC13{slash}TAMPER-RTC-Pad2)") (class "Default")
      (node (ref "U5") (pin "2") (pinfunction "PC13/TAMPER-RTC_2") (pintype "passive+no_connect"))
    )
    (net (code "106") (name "unconnected-(U5-PC14{slash}OSC32_IN-Pad3)") (class "Default")
      (node (ref "U5") (pin "3") (pinfunction "PC14/OSC32_IN_3") (pintype "passive+no_connect"))
    )
    (net (code "107") (name "unconnected-(U5-PC15{slash}OSC32_OUT-Pad4)") (class "Default")
      (node (ref "U5") (pin "4") (pinfunction "PC15/OSC32_OUT_4") (pintype "passive+no_connect"))
    )
    (net (code "108") (name "unconnected-(U17-AUX_CL-Pad7)") (class "Default")
      (node (ref "U17") (pin "7") (pinfunction "AUX_CL_7") (pintype "passive+no_connect"))
    )
    (net (code "109") (name "unconnected-(U17-AUX_DA-Pad6)") (class "Default")
      (node (ref "U17") (pin "6") (pinfunction "AUX_DA_6") (pintype "passive+no_connect"))
    )
    (net (code "110") (name "unconnected-(U17-INT-Pad12)") (class "Default")
      (node (ref "U17") (pin "12") (pinfunction "INT_12") (pintype "passive+no_connect"))
    )
    (net (code "111") (name "unconnected-(U17-NC-Pad2)") (class "Default")
      (node (ref "U17") (pin "2") (pinfunction "NC_2") (pintype "passive+no_connect"))
    )
    (net (code "112") (name "unconnected-(U17-NC-Pad3)") (class "Default")
      (node (ref "U17") (pin "3") (pinfunction "NC_3") (pintype "passive+no_connect"))
    )
    (net (code "113") (name "unconnected-(U17-NC-Pad4)") (class "Default")
      (node (ref "U17") (pin "4") (pinfunction "NC_4") (pintype "passive+no_connect"))
    )
    (net (code "114") (name "unconnected-(U17-NC-Pad5)") (class "Default")
      (node (ref "U17") (pin "5") (pinfunction "NC_5") (pintype "passive+no_connect"))
    )
    (net (code "115") (name "unconnected-(U17-NC-Pad14)") (class "Default")
      (node (ref "U17") (pin "14") (pinfunction "NC_14") (pintype "passive+no_connect"))
    )
    (net (code "116") (name "unconnected-(U17-NC-Pad15)") (class "Default")
      (node (ref "U17") (pin "15") (pinfunction "NC_15") (pintype "passive+no_connect"))
    )
    (net (code "117") (name "unconnected-(U17-NC-Pad16)") (class "Default")
      (node (ref "U17") (pin "16") (pinfunction "NC_16") (pintype "passive+no_connect"))
    )
    (net (code "118") (name "unconnected-(U17-NC-Pad17)") (class "Default")
      (node (ref "U17") (pin "17") (pinfunction "NC_17") (pintype "passive+no_connect"))
    )
    (net (code "119") (name "unconnected-(U17-RESV-Pad19)") (class "Default")
      (node (ref "U17") (pin "19") (pinfunction "RESV_19") (pintype "passive+no_connect"))
    )
    (net (code "120") (name "unconnected-(U17-RESV-Pad21)") (class "Default")
      (node (ref "U17") (pin "21") (pinfunction "RESV_21") (pintype "passive+no_connect"))
    )
    (net (code "121") (name "unconnected-(U17-RESV-Pad22)") (class "Default")
      (node (ref "U17") (pin "22") (pinfunction "RESV_22") (pintype "passive+no_connect"))
    )
  )
)
